# MainDAC.net
KiCad netlist of a schematic drawn in Altium Designer
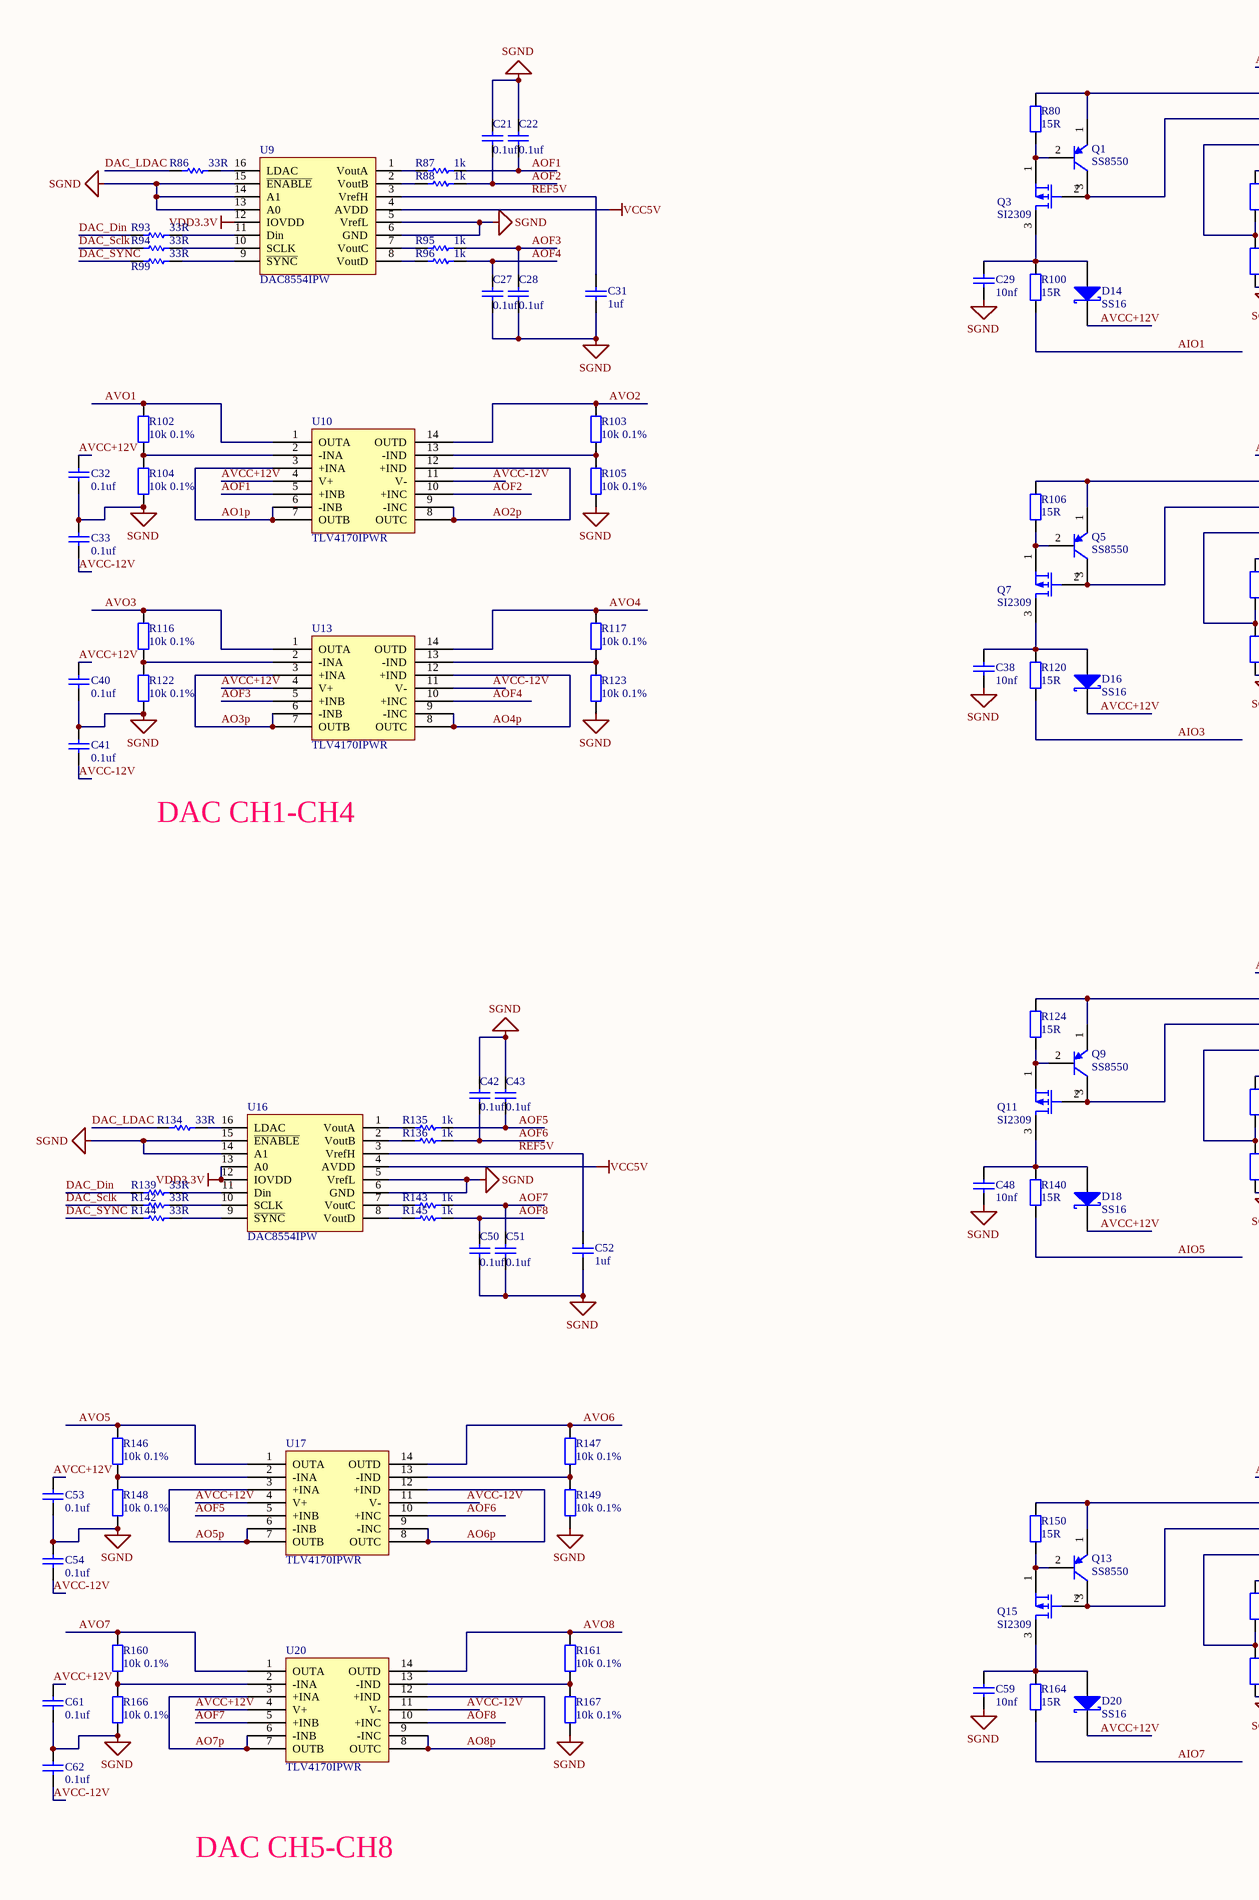
[diagram p0: MainDAC.SchDoc, left]
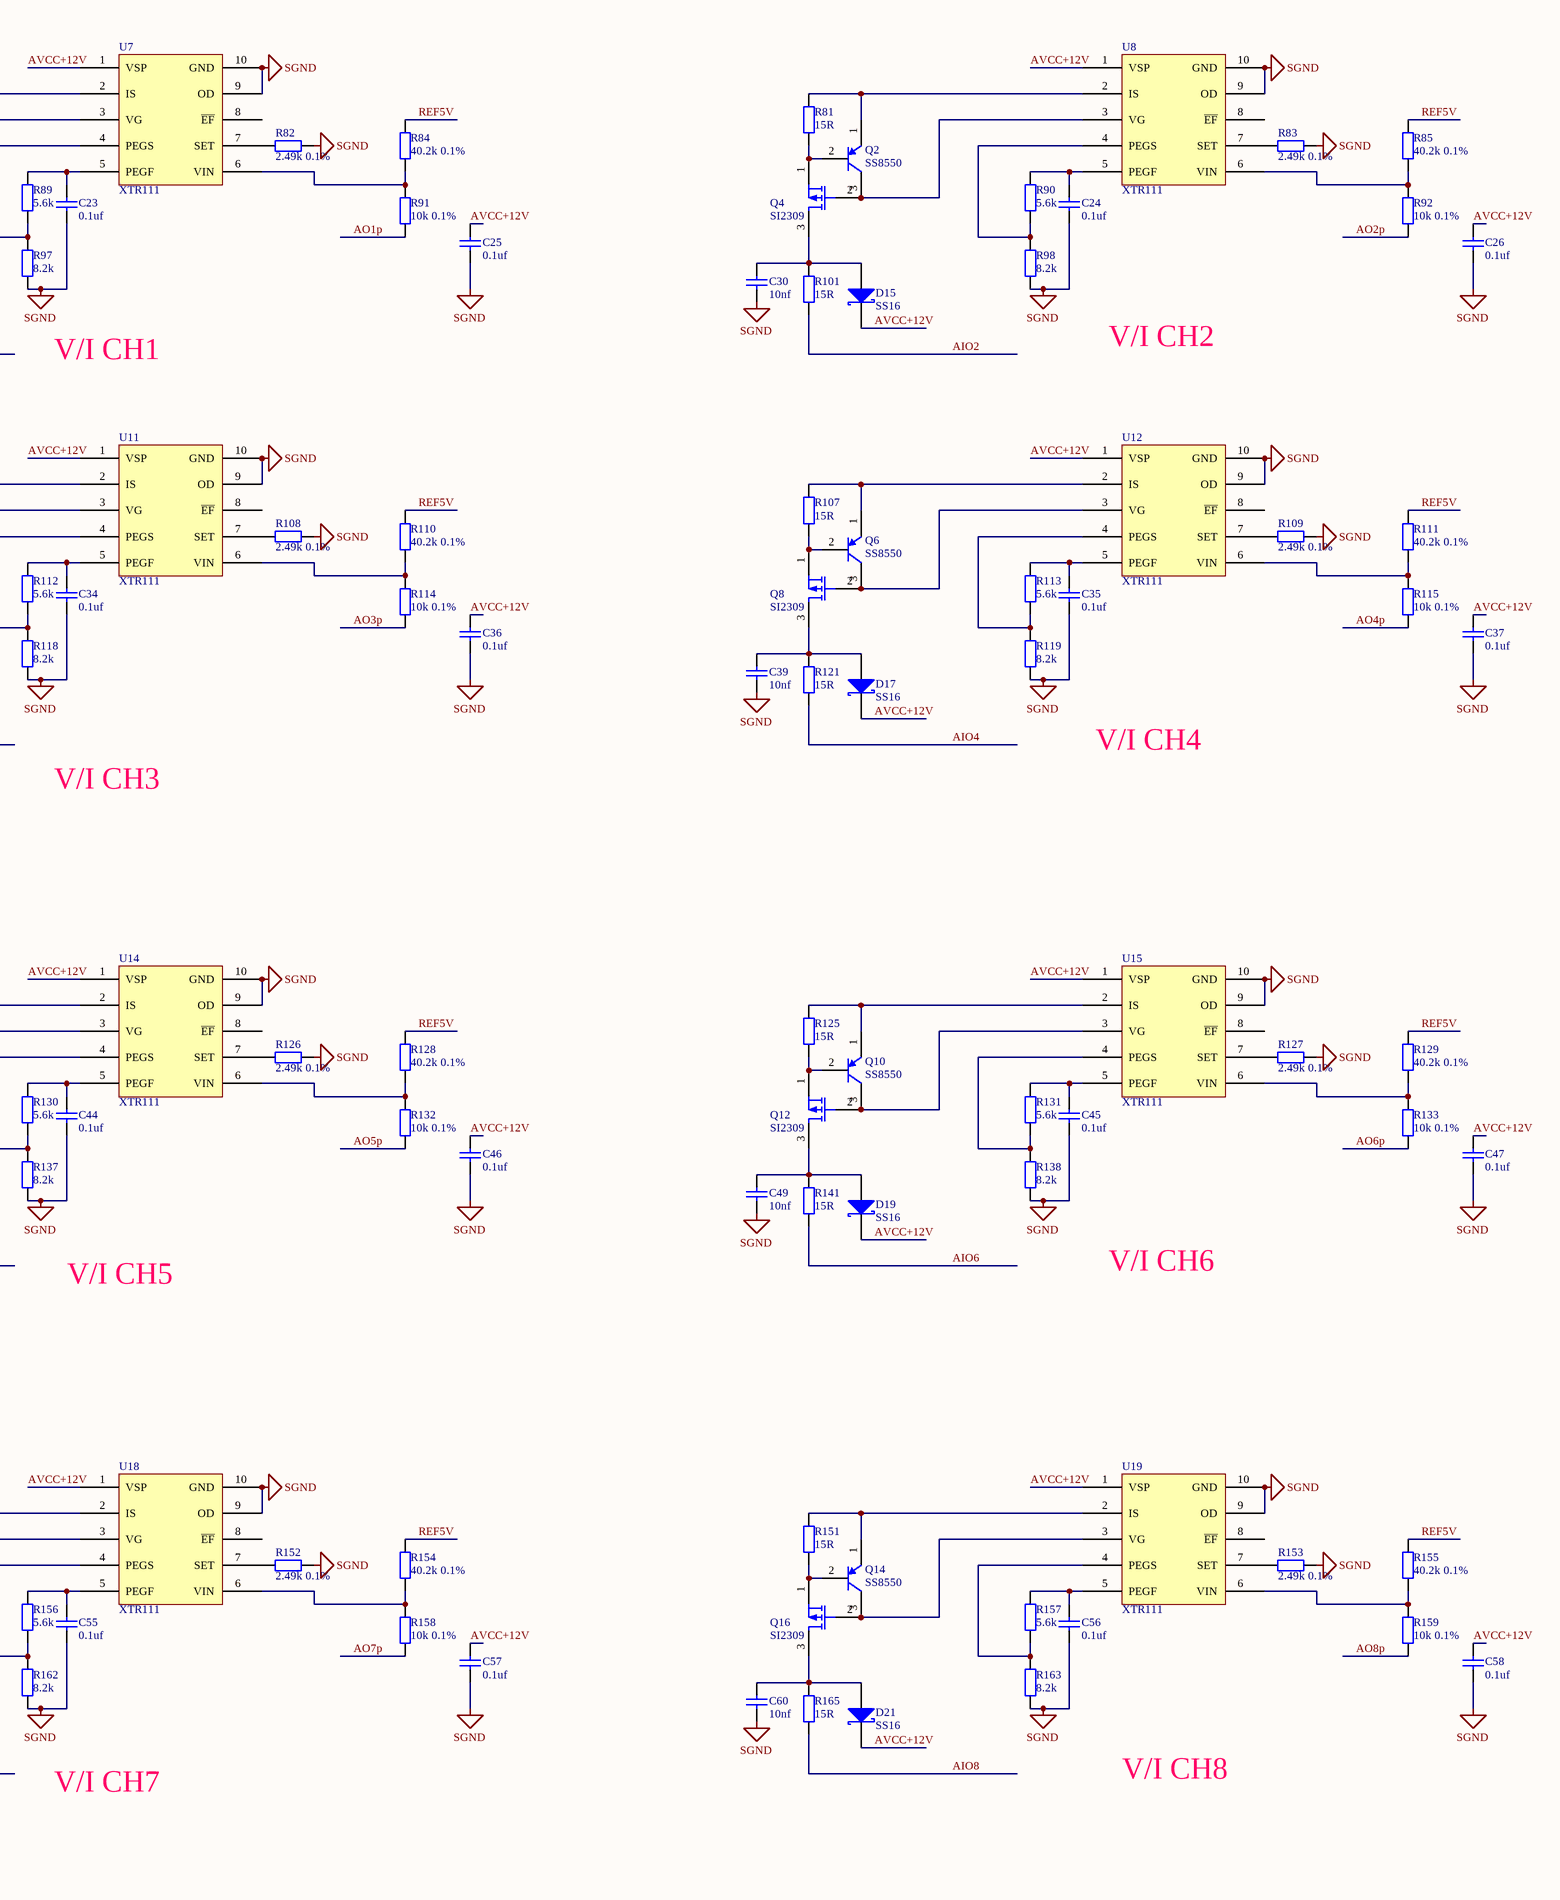
[diagram p1: MainDAC.SchDoc, right]

(export (version "E")
  (design (tool "Eeschema 10.0.6"))
  (components
    (comp (ref "C21")
      (value "0.1uf")
      (footprint "C0805")
      (description "Capacitor")
      (fields
        (field (name "MANUFACTURER") "Generic Components")
        (field (name "Comment") "Cap")
        (field (name "PUBLISHER") "Altium Hobart Technology Centre")
      )
      (libsource (lib "Miscellaneous Devices") (part "Cap"))
    )
    (comp (ref "C22")
      (value "0.1uf")
      (footprint "C0805")
      (description "Capacitor")
      (fields
        (field (name "MANUFACTURER") "Generic Components")
        (field (name "Comment") "Cap")
        (field (name "PUBLISHER") "Altium Hobart Technology Centre")
      )
      (libsource (lib "Miscellaneous Devices") (part "Cap"))
    )
    (comp (ref "C23")
      (value "0.1uf")
      (footprint "C0805")
      (description "Capacitor")
      (fields
        (field (name "MANUFACTURER") "Generic Components")
        (field (name "Comment") "Cap")
        (field (name "PUBLISHER") "Altium Hobart Technology Centre")
      )
      (libsource (lib "Miscellaneous Devices") (part "Cap"))
    )
    (comp (ref "C24")
      (value "0.1uf")
      (footprint "C0805")
      (description "Capacitor")
      (fields
        (field (name "MANUFACTURER") "Generic Components")
        (field (name "Comment") "Cap")
        (field (name "PUBLISHER") "Altium Hobart Technology Centre")
      )
      (libsource (lib "Miscellaneous Devices") (part "Cap"))
    )
    (comp (ref "C25")
      (value "0.1uf")
      (footprint "C0805")
      (description "Capacitor")
      (fields
        (field (name "MANUFACTURER") "Generic Components")
        (field (name "Comment") "Cap")
        (field (name "PUBLISHER") "Altium Hobart Technology Centre")
      )
      (libsource (lib "Miscellaneous Devices") (part "Cap"))
    )
    (comp (ref "C26")
      (value "0.1uf")
      (footprint "C0805")
      (description "Capacitor")
      (fields
        (field (name "MANUFACTURER") "Generic Components")
        (field (name "Comment") "Cap")
        (field (name "PUBLISHER") "Altium Hobart Technology Centre")
      )
      (libsource (lib "Miscellaneous Devices") (part "Cap"))
    )
    (comp (ref "C27")
      (value "0.1uf")
      (footprint "C0805")
      (description "Capacitor")
      (fields
        (field (name "MANUFACTURER") "Generic Components")
        (field (name "Comment") "Cap")
        (field (name "PUBLISHER") "Altium Hobart Technology Centre")
      )
      (libsource (lib "Miscellaneous Devices") (part "Cap"))
    )
    (comp (ref "C28")
      (value "0.1uf")
      (footprint "C0805")
      (description "Capacitor")
      (fields
        (field (name "MANUFACTURER") "Generic Components")
        (field (name "Comment") "Cap")
        (field (name "PUBLISHER") "Altium Hobart Technology Centre")
      )
      (libsource (lib "Miscellaneous Devices") (part "Cap"))
    )
    (comp (ref "C29")
      (value "10nf")
      (footprint "C0805")
      (description "Capacitor")
      (fields
        (field (name "MANUFACTURER") "Generic Components")
        (field (name "Comment") "Cap")
        (field (name "PUBLISHER") "Altium Hobart Technology Centre")
      )
      (libsource (lib "Miscellaneous Devices") (part "Cap"))
    )
    (comp (ref "C30")
      (value "10nf")
      (footprint "C0805")
      (description "Capacitor")
      (fields
        (field (name "MANUFACTURER") "Generic Components")
        (field (name "Comment") "Cap")
        (field (name "PUBLISHER") "Altium Hobart Technology Centre")
      )
      (libsource (lib "Miscellaneous Devices") (part "Cap"))
    )
    (comp (ref "C31")
      (value "1uf")
      (footprint "C0805")
      (description "Capacitor")
      (fields
        (field (name "MANUFACTURER") "Generic Components")
        (field (name "Comment") "Cap")
        (field (name "PUBLISHER") "Altium Hobart Technology Centre")
      )
      (libsource (lib "Miscellaneous Devices") (part "Cap"))
    )
    (comp (ref "C32")
      (value "0.1uf")
      (footprint "C0805")
      (description "Capacitor")
      (fields
        (field (name "MANUFACTURER") "Generic Components")
        (field (name "Comment") "Cap")
        (field (name "PUBLISHER") "Altium Hobart Technology Centre")
      )
      (libsource (lib "Miscellaneous Devices") (part "Cap"))
    )
    (comp (ref "C33")
      (value "0.1uf")
      (footprint "C0805")
      (description "Capacitor")
      (fields
        (field (name "MANUFACTURER") "Generic Components")
        (field (name "Comment") "Cap")
        (field (name "PUBLISHER") "Altium Hobart Technology Centre")
      )
      (libsource (lib "Miscellaneous Devices") (part "Cap"))
    )
    (comp (ref "C34")
      (value "0.1uf")
      (footprint "C0805")
      (description "Capacitor")
      (fields
        (field (name "MANUFACTURER") "Generic Components")
        (field (name "Comment") "Cap")
        (field (name "PUBLISHER") "Altium Hobart Technology Centre")
      )
      (libsource (lib "Miscellaneous Devices") (part "Cap"))
    )
    (comp (ref "C35")
      (value "0.1uf")
      (footprint "C0805")
      (description "Capacitor")
      (fields
        (field (name "MANUFACTURER") "Generic Components")
        (field (name "Comment") "Cap")
        (field (name "PUBLISHER") "Altium Hobart Technology Centre")
      )
      (libsource (lib "Miscellaneous Devices") (part "Cap"))
    )
    (comp (ref "C36")
      (value "0.1uf")
      (footprint "C0805")
      (description "Capacitor")
      (fields
        (field (name "MANUFACTURER") "Generic Components")
        (field (name "Comment") "Cap")
        (field (name "PUBLISHER") "Altium Hobart Technology Centre")
      )
      (libsource (lib "Miscellaneous Devices") (part "Cap"))
    )
    (comp (ref "C37")
      (value "0.1uf")
      (footprint "C0805")
      (description "Capacitor")
      (fields
        (field (name "MANUFACTURER") "Generic Components")
        (field (name "Comment") "Cap")
        (field (name "PUBLISHER") "Altium Hobart Technology Centre")
      )
      (libsource (lib "Miscellaneous Devices") (part "Cap"))
    )
    (comp (ref "C38")
      (value "10nf")
      (footprint "C0805")
      (description "Capacitor")
      (fields
        (field (name "MANUFACTURER") "Generic Components")
        (field (name "Comment") "Cap")
        (field (name "PUBLISHER") "Altium Hobart Technology Centre")
      )
      (libsource (lib "Miscellaneous Devices") (part "Cap"))
    )
    (comp (ref "C39")
      (value "10nf")
      (footprint "C0805")
      (description "Capacitor")
      (fields
        (field (name "MANUFACTURER") "Generic Components")
        (field (name "Comment") "Cap")
        (field (name "PUBLISHER") "Altium Hobart Technology Centre")
      )
      (libsource (lib "Miscellaneous Devices") (part "Cap"))
    )
    (comp (ref "C40")
      (value "0.1uf")
      (footprint "C0805")
      (description "Capacitor")
      (fields
        (field (name "MANUFACTURER") "Generic Components")
        (field (name "Comment") "Cap")
        (field (name "PUBLISHER") "Altium Hobart Technology Centre")
      )
      (libsource (lib "Miscellaneous Devices") (part "Cap"))
    )
    (comp (ref "C41")
      (value "0.1uf")
      (footprint "C0805")
      (description "Capacitor")
      (fields
        (field (name "MANUFACTURER") "Generic Components")
        (field (name "Comment") "Cap")
        (field (name "PUBLISHER") "Altium Hobart Technology Centre")
      )
      (libsource (lib "Miscellaneous Devices") (part "Cap"))
    )
    (comp (ref "C42")
      (value "0.1uf")
      (footprint "C0805")
      (description "Capacitor")
      (fields
        (field (name "MANUFACTURER") "Generic Components")
        (field (name "Comment") "Cap")
        (field (name "PUBLISHER") "Altium Hobart Technology Centre")
      )
      (libsource (lib "Miscellaneous Devices") (part "Cap"))
    )
    (comp (ref "C43")
      (value "0.1uf")
      (footprint "C0805")
      (description "Capacitor")
      (fields
        (field (name "MANUFACTURER") "Generic Components")
        (field (name "Comment") "Cap")
        (field (name "PUBLISHER") "Altium Hobart Technology Centre")
      )
      (libsource (lib "Miscellaneous Devices") (part "Cap"))
    )
    (comp (ref "C44")
      (value "0.1uf")
      (footprint "C0805")
      (description "Capacitor")
      (fields
        (field (name "MANUFACTURER") "Generic Components")
        (field (name "Comment") "Cap")
        (field (name "PUBLISHER") "Altium Hobart Technology Centre")
      )
      (libsource (lib "Miscellaneous Devices") (part "Cap"))
    )
    (comp (ref "C45")
      (value "0.1uf")
      (footprint "C0805")
      (description "Capacitor")
      (fields
        (field (name "MANUFACTURER") "Generic Components")
        (field (name "Comment") "Cap")
        (field (name "PUBLISHER") "Altium Hobart Technology Centre")
      )
      (libsource (lib "Miscellaneous Devices") (part "Cap"))
    )
    (comp (ref "C46")
      (value "0.1uf")
      (footprint "C0805")
      (description "Capacitor")
      (fields
        (field (name "MANUFACTURER") "Generic Components")
        (field (name "Comment") "Cap")
        (field (name "PUBLISHER") "Altium Hobart Technology Centre")
      )
      (libsource (lib "Miscellaneous Devices") (part "Cap"))
    )
    (comp (ref "C47")
      (value "0.1uf")
      (footprint "C0805")
      (description "Capacitor")
      (fields
        (field (name "MANUFACTURER") "Generic Components")
        (field (name "Comment") "Cap")
        (field (name "PUBLISHER") "Altium Hobart Technology Centre")
      )
      (libsource (lib "Miscellaneous Devices") (part "Cap"))
    )
    (comp (ref "C48")
      (value "10nf")
      (footprint "C0805")
      (description "Capacitor")
      (fields
        (field (name "MANUFACTURER") "Generic Components")
        (field (name "Comment") "Cap")
        (field (name "PUBLISHER") "Altium Hobart Technology Centre")
      )
      (libsource (lib "Miscellaneous Devices") (part "Cap"))
    )
    (comp (ref "C49")
      (value "10nf")
      (footprint "C0805")
      (description "Capacitor")
      (fields
        (field (name "MANUFACTURER") "Generic Components")
        (field (name "Comment") "Cap")
        (field (name "PUBLISHER") "Altium Hobart Technology Centre")
      )
      (libsource (lib "Miscellaneous Devices") (part "Cap"))
    )
    (comp (ref "C50")
      (value "0.1uf")
      (footprint "C0805")
      (description "Capacitor")
      (fields
        (field (name "MANUFACTURER") "Generic Components")
        (field (name "Comment") "Cap")
        (field (name "PUBLISHER") "Altium Hobart Technology Centre")
      )
      (libsource (lib "Miscellaneous Devices") (part "Cap"))
    )
    (comp (ref "C51")
      (value "0.1uf")
      (footprint "C0805")
      (description "Capacitor")
      (fields
        (field (name "MANUFACTURER") "Generic Components")
        (field (name "Comment") "Cap")
        (field (name "PUBLISHER") "Altium Hobart Technology Centre")
      )
      (libsource (lib "Miscellaneous Devices") (part "Cap"))
    )
    (comp (ref "C52")
      (value "1uf")
      (footprint "C0805")
      (description "Capacitor")
      (fields
        (field (name "MANUFACTURER") "Generic Components")
        (field (name "Comment") "Cap")
        (field (name "PUBLISHER") "Altium Hobart Technology Centre")
      )
      (libsource (lib "Miscellaneous Devices") (part "Cap"))
    )
    (comp (ref "C53")
      (value "0.1uf")
      (footprint "C0805")
      (description "Capacitor")
      (fields
        (field (name "MANUFACTURER") "Generic Components")
        (field (name "Comment") "Cap")
        (field (name "PUBLISHER") "Altium Hobart Technology Centre")
      )
      (libsource (lib "Miscellaneous Devices") (part "Cap"))
    )
    (comp (ref "C54")
      (value "0.1uf")
      (footprint "C0805")
      (description "Capacitor")
      (fields
        (field (name "MANUFACTURER") "Generic Components")
        (field (name "Comment") "Cap")
        (field (name "PUBLISHER") "Altium Hobart Technology Centre")
      )
      (libsource (lib "Miscellaneous Devices") (part "Cap"))
    )
    (comp (ref "C55")
      (value "0.1uf")
      (footprint "C0805")
      (description "Capacitor")
      (fields
        (field (name "MANUFACTURER") "Generic Components")
        (field (name "Comment") "Cap")
        (field (name "PUBLISHER") "Altium Hobart Technology Centre")
      )
      (libsource (lib "Miscellaneous Devices") (part "Cap"))
    )
    (comp (ref "C56")
      (value "0.1uf")
      (footprint "C0805")
      (description "Capacitor")
      (fields
        (field (name "MANUFACTURER") "Generic Components")
        (field (name "Comment") "Cap")
        (field (name "PUBLISHER") "Altium Hobart Technology Centre")
      )
      (libsource (lib "Miscellaneous Devices") (part "Cap"))
    )
    (comp (ref "C57")
      (value "0.1uf")
      (footprint "C0805")
      (description "Capacitor")
      (fields
        (field (name "MANUFACTURER") "Generic Components")
        (field (name "Comment") "Cap")
        (field (name "PUBLISHER") "Altium Hobart Technology Centre")
      )
      (libsource (lib "Miscellaneous Devices") (part "Cap"))
    )
    (comp (ref "C58")
      (value "0.1uf")
      (footprint "C0805")
      (description "Capacitor")
      (fields
        (field (name "MANUFACTURER") "Generic Components")
        (field (name "Comment") "Cap")
        (field (name "PUBLISHER") "Altium Hobart Technology Centre")
      )
      (libsource (lib "Miscellaneous Devices") (part "Cap"))
    )
    (comp (ref "C59")
      (value "10nf")
      (footprint "C0805")
      (description "Capacitor")
      (fields
        (field (name "MANUFACTURER") "Generic Components")
        (field (name "Comment") "Cap")
        (field (name "PUBLISHER") "Altium Hobart Technology Centre")
      )
      (libsource (lib "Miscellaneous Devices") (part "Cap"))
    )
    (comp (ref "C60")
      (value "10nf")
      (footprint "C0805")
      (description "Capacitor")
      (fields
        (field (name "MANUFACTURER") "Generic Components")
        (field (name "Comment") "Cap")
        (field (name "PUBLISHER") "Altium Hobart Technology Centre")
      )
      (libsource (lib "Miscellaneous Devices") (part "Cap"))
    )
    (comp (ref "C61")
      (value "0.1uf")
      (footprint "C0805")
      (description "Capacitor")
      (fields
        (field (name "MANUFACTURER") "Generic Components")
        (field (name "Comment") "Cap")
        (field (name "PUBLISHER") "Altium Hobart Technology Centre")
      )
      (libsource (lib "Miscellaneous Devices") (part "Cap"))
    )
    (comp (ref "C62")
      (value "0.1uf")
      (footprint "C0805")
      (description "Capacitor")
      (fields
        (field (name "MANUFACTURER") "Generic Components")
        (field (name "Comment") "Cap")
        (field (name "PUBLISHER") "Altium Hobart Technology Centre")
      )
      (libsource (lib "Miscellaneous Devices") (part "Cap"))
    )
    (comp (ref "D14")
      (value "SS16")
      (footprint "SMB")
      (description "Schottky Diode")
      (fields (field (name "PUBLISHER") "Altium Limited"))
      (libsource (lib "Miscellaneous Devices") (part "D Schottky"))
    )
    (comp (ref "D15")
      (value "SS16")
      (footprint "SMB")
      (description "Schottky Diode")
      (fields (field (name "PUBLISHER") "Altium Limited"))
      (libsource (lib "Miscellaneous Devices") (part "D Schottky"))
    )
    (comp (ref "D16")
      (value "SS16")
      (footprint "SMB")
      (description "Schottky Diode")
      (fields (field (name "PUBLISHER") "Altium Limited"))
      (libsource (lib "Miscellaneous Devices") (part "D Schottky"))
    )
    (comp (ref "D17")
      (value "SS16")
      (footprint "SMB")
      (description "Schottky Diode")
      (fields (field (name "PUBLISHER") "Altium Limited"))
      (libsource (lib "Miscellaneous Devices") (part "D Schottky"))
    )
    (comp (ref "D18")
      (value "SS16")
      (footprint "SMB")
      (description "Schottky Diode")
      (fields (field (name "PUBLISHER") "Altium Limited"))
      (libsource (lib "Miscellaneous Devices") (part "D Schottky"))
    )
    (comp (ref "D19")
      (value "SS16")
      (footprint "SMB")
      (description "Schottky Diode")
      (fields (field (name "PUBLISHER") "Altium Limited"))
      (libsource (lib "Miscellaneous Devices") (part "D Schottky"))
    )
    (comp (ref "D20")
      (value "SS16")
      (footprint "SMB")
      (description "Schottky Diode")
      (fields (field (name "PUBLISHER") "Altium Limited"))
      (libsource (lib "Miscellaneous Devices") (part "D Schottky"))
    )
    (comp (ref "D21")
      (value "SS16")
      (footprint "SMB")
      (description "Schottky Diode")
      (fields (field (name "PUBLISHER") "Altium Limited"))
      (libsource (lib "Miscellaneous Devices") (part "D Schottky"))
    )
    (comp (ref "Q1")
      (value "SS8550")
      (footprint "sot-23")
      (description "PNP General Purpose Amplifier")
      (fields (field (name "PUBLISHER") "Altium Limited"))
      (libsource (lib "Miscellaneous Devices") (part "2N3906"))
    )
    (comp (ref "Q2")
      (value "SS8550")
      (footprint "sot-23")
      (description "PNP General Purpose Amplifier")
      (fields (field (name "PUBLISHER") "Altium Limited"))
      (libsource (lib "Miscellaneous Devices") (part "2N3906"))
    )
    (comp (ref "Q3")
      (value "SI2309")
      (footprint "sot-23")
      (description "P-Channel MOSFET")
      (fields (field (name "PUBLISHER") "Altium Limited"))
      (libsource (lib "Miscellaneous Devices") (part "MOSFET-P"))
    )
    (comp (ref "Q4")
      (value "SI2309")
      (footprint "sot-23")
      (description "P-Channel MOSFET")
      (fields (field (name "PUBLISHER") "Altium Limited"))
      (libsource (lib "Miscellaneous Devices") (part "MOSFET-P"))
    )
    (comp (ref "Q5")
      (value "SS8550")
      (footprint "sot-23")
      (description "PNP General Purpose Amplifier")
      (fields (field (name "PUBLISHER") "Altium Limited"))
      (libsource (lib "Miscellaneous Devices") (part "2N3906"))
    )
    (comp (ref "Q6")
      (value "SS8550")
      (footprint "sot-23")
      (description "PNP General Purpose Amplifier")
      (fields (field (name "PUBLISHER") "Altium Limited"))
      (libsource (lib "Miscellaneous Devices") (part "2N3906"))
    )
    (comp (ref "Q7")
      (value "SI2309")
      (footprint "sot-23")
      (description "P-Channel MOSFET")
      (fields (field (name "PUBLISHER") "Altium Limited"))
      (libsource (lib "Miscellaneous Devices") (part "MOSFET-P"))
    )
    (comp (ref "Q8")
      (value "SI2309")
      (footprint "sot-23")
      (description "P-Channel MOSFET")
      (fields (field (name "PUBLISHER") "Altium Limited"))
      (libsource (lib "Miscellaneous Devices") (part "MOSFET-P"))
    )
    (comp (ref "Q9")
      (value "SS8550")
      (footprint "sot-23")
      (description "PNP General Purpose Amplifier")
      (fields (field (name "PUBLISHER") "Altium Limited"))
      (libsource (lib "Miscellaneous Devices") (part "2N3906"))
    )
    (comp (ref "Q10")
      (value "SS8550")
      (footprint "sot-23")
      (description "PNP General Purpose Amplifier")
      (fields (field (name "PUBLISHER") "Altium Limited"))
      (libsource (lib "Miscellaneous Devices") (part "2N3906"))
    )
    (comp (ref "Q11")
      (value "SI2309")
      (footprint "sot-23")
      (description "P-Channel MOSFET")
      (fields (field (name "PUBLISHER") "Altium Limited"))
      (libsource (lib "Miscellaneous Devices") (part "MOSFET-P"))
    )
    (comp (ref "Q12")
      (value "SI2309")
      (footprint "sot-23")
      (description "P-Channel MOSFET")
      (fields (field (name "PUBLISHER") "Altium Limited"))
      (libsource (lib "Miscellaneous Devices") (part "MOSFET-P"))
    )
    (comp (ref "Q13")
      (value "SS8550")
      (footprint "sot-23")
      (description "PNP General Purpose Amplifier")
      (fields (field (name "PUBLISHER") "Altium Limited"))
      (libsource (lib "Miscellaneous Devices") (part "2N3906"))
    )
    (comp (ref "Q14")
      (value "SS8550")
      (footprint "sot-23")
      (description "PNP General Purpose Amplifier")
      (fields (field (name "PUBLISHER") "Altium Limited"))
      (libsource (lib "Miscellaneous Devices") (part "2N3906"))
    )
    (comp (ref "Q15")
      (value "SI2309")
      (footprint "sot-23")
      (description "P-Channel MOSFET")
      (fields (field (name "PUBLISHER") "Altium Limited"))
      (libsource (lib "Miscellaneous Devices") (part "MOSFET-P"))
    )
    (comp (ref "Q16")
      (value "SI2309")
      (footprint "sot-23")
      (description "P-Channel MOSFET")
      (fields (field (name "PUBLISHER") "Altium Limited"))
      (libsource (lib "Miscellaneous Devices") (part "MOSFET-P"))
    )
    (comp (ref "R80")
      (value "15R")
      (footprint "0805")
      (fields (field (name "Comment") "Res2"))
      (libsource (lib "S1") (part "RES"))
    )
    (comp (ref "R81")
      (value "15R")
      (footprint "0805")
      (fields (field (name "Comment") "Res2"))
      (libsource (lib "S1") (part "RES"))
    )
    (comp (ref "R82")
      (value "2.49k 0.1%")
      (footprint "0805")
      (fields (field (name "Comment") "Res2"))
      (libsource (lib "") (part "RES_2"))
    )
    (comp (ref "R83")
      (value "2.49k 0.1%")
      (footprint "0805")
      (fields (field (name "Comment") "Res2"))
      (libsource (lib "") (part "RES_2"))
    )
    (comp (ref "R84")
      (value "40.2k 0.1%")
      (footprint "0805")
      (fields (field (name "Comment") "Res2"))
      (libsource (lib "S1") (part "RES"))
    )
    (comp (ref "R85")
      (value "40.2k 0.1%")
      (footprint "0805")
      (fields (field (name "Comment") "Res2"))
      (libsource (lib "S1") (part "RES"))
    )
    (comp (ref "R86")
      (value "33R")
      (footprint "0805")
      (description "Semiconductor Resistor")
      (fields (field (name "Comment") "Res Semi") (field (name "PUBLISHER") "Altium Limited"))
      (libsource (lib "Miscellaneous Devices") (part "Res Semi"))
    )
    (comp (ref "R87")
      (value "1k")
      (footprint "0805")
      (description "Semiconductor Resistor")
      (fields (field (name "Comment") "Res Semi") (field (name "PUBLISHER") "Altium Limited"))
      (libsource (lib "Miscellaneous Devices") (part "Res Semi"))
    )
    (comp (ref "R88")
      (value "1k")
      (footprint "0805")
      (description "Semiconductor Resistor")
      (fields (field (name "Comment") "Res Semi") (field (name "PUBLISHER") "Altium Limited"))
      (libsource (lib "Miscellaneous Devices") (part "Res Semi"))
    )
    (comp (ref "R89")
      (value "5.6k")
      (footprint "0805")
      (fields (field (name "Comment") "Res2"))
      (libsource (lib "S1") (part "RES"))
    )
    (comp (ref "R90")
      (value "5.6k")
      (footprint "0805")
      (fields (field (name "Comment") "Res2"))
      (libsource (lib "S1") (part "RES"))
    )
    (comp (ref "R91")
      (value "10k 0.1%")
      (footprint "0805")
      (fields (field (name "Comment") "Res2"))
      (libsource (lib "S1") (part "RES"))
    )
    (comp (ref "R92")
      (value "10k 0.1%")
      (footprint "0805")
      (fields (field (name "Comment") "Res2"))
      (libsource (lib "S1") (part "RES"))
    )
    (comp (ref "R93")
      (value "33R")
      (footprint "0805")
      (description "Semiconductor Resistor")
      (fields (field (name "Comment") "Res Semi") (field (name "PUBLISHER") "Altium Limited"))
      (libsource (lib "Miscellaneous Devices") (part "Res Semi"))
    )
    (comp (ref "R94")
      (value "33R")
      (footprint "0805")
      (description "Semiconductor Resistor")
      (fields (field (name "Comment") "Res Semi") (field (name "PUBLISHER") "Altium Limited"))
      (libsource (lib "Miscellaneous Devices") (part "Res Semi"))
    )
    (comp (ref "R95")
      (value "1k")
      (footprint "0805")
      (description "Semiconductor Resistor")
      (fields (field (name "Comment") "Res Semi") (field (name "PUBLISHER") "Altium Limited"))
      (libsource (lib "Miscellaneous Devices") (part "Res Semi"))
    )
    (comp (ref "R96")
      (value "1k")
      (footprint "0805")
      (description "Semiconductor Resistor")
      (fields (field (name "Comment") "Res Semi") (field (name "PUBLISHER") "Altium Limited"))
      (libsource (lib "Miscellaneous Devices") (part "Res Semi"))
    )
    (comp (ref "R97")
      (value "8.2k")
      (footprint "0805")
      (fields (field (name "Comment") "Res2"))
      (libsource (lib "S1") (part "RES"))
    )
    (comp (ref "R98")
      (value "8.2k")
      (footprint "0805")
      (fields (field (name "Comment") "Res2"))
      (libsource (lib "S1") (part "RES"))
    )
    (comp (ref "R99")
      (value "33R")
      (footprint "0805")
      (description "Semiconductor Resistor")
      (fields (field (name "Comment") "Res Semi") (field (name "PUBLISHER") "Altium Limited"))
      (libsource (lib "Miscellaneous Devices") (part "Res Semi"))
    )
    (comp (ref "R100")
      (value "15R")
      (footprint "0805")
      (fields (field (name "Comment") "Res2"))
      (libsource (lib "S1") (part "RES"))
    )
    (comp (ref "R101")
      (value "15R")
      (footprint "0805")
      (fields (field (name "Comment") "Res2"))
      (libsource (lib "S1") (part "RES"))
    )
    (comp (ref "R102")
      (value "10k 0.1%")
      (footprint "0805")
      (fields (field (name "Comment") "Res2"))
      (libsource (lib "") (part "RES_1"))
    )
    (comp (ref "R103")
      (value "10k 0.1%")
      (footprint "0805")
      (fields (field (name "Comment") "Res2"))
      (libsource (lib "S1") (part "RES"))
    )
    (comp (ref "R104")
      (value "10k 0.1%")
      (footprint "0805")
      (fields (field (name "Comment") "Res2"))
      (libsource (lib "") (part "RES_1"))
    )
    (comp (ref "R105")
      (value "10k 0.1%")
      (footprint "0805")
      (fields (field (name "Comment") "Res2"))
      (libsource (lib "S1") (part "RES"))
    )
    (comp (ref "R106")
      (value "15R")
      (footprint "0805")
      (fields (field (name "Comment") "Res2"))
      (libsource (lib "S1") (part "RES"))
    )
    (comp (ref "R107")
      (value "15R")
      (footprint "0805")
      (fields (field (name "Comment") "Res2"))
      (libsource (lib "S1") (part "RES"))
    )
    (comp (ref "R108")
      (value "2.49k 0.1%")
      (footprint "0805")
      (fields (field (name "Comment") "Res2"))
      (libsource (lib "") (part "RES_2"))
    )
    (comp (ref "R109")
      (value "2.49k 0.1%")
      (footprint "0805")
      (fields (field (name "Comment") "Res2"))
      (libsource (lib "") (part "RES_2"))
    )
    (comp (ref "R110")
      (value "40.2k 0.1%")
      (footprint "0805")
      (fields (field (name "Comment") "Res2"))
      (libsource (lib "S1") (part "RES"))
    )
    (comp (ref "R111")
      (value "40.2k 0.1%")
      (footprint "0805")
      (fields (field (name "Comment") "Res2"))
      (libsource (lib "S1") (part "RES"))
    )
    (comp (ref "R112")
      (value "5.6k")
      (footprint "0805")
      (fields (field (name "Comment") "Res2"))
      (libsource (lib "S1") (part "RES"))
    )
    (comp (ref "R113")
      (value "5.6k")
      (footprint "0805")
      (fields (field (name "Comment") "Res2"))
      (libsource (lib "S1") (part "RES"))
    )
    (comp (ref "R114")
      (value "10k 0.1%")
      (footprint "0805")
      (fields (field (name "Comment") "Res2"))
      (libsource (lib "S1") (part "RES"))
    )
    (comp (ref "R115")
      (value "10k 0.1%")
      (footprint "0805")
      (fields (field (name "Comment") "Res2"))
      (libsource (lib "S1") (part "RES"))
    )
    (comp (ref "R116")
      (value "10k 0.1%")
      (footprint "0805")
      (fields (field (name "Comment") "Res2"))
      (libsource (lib "") (part "RES_1"))
    )
    (comp (ref "R117")
      (value "10k 0.1%")
      (footprint "0805")
      (fields (field (name "Comment") "Res2"))
      (libsource (lib "S1") (part "RES"))
    )
    (comp (ref "R118")
      (value "8.2k")
      (footprint "0805")
      (fields (field (name "Comment") "Res2"))
      (libsource (lib "S1") (part "RES"))
    )
    (comp (ref "R119")
      (value "8.2k")
      (footprint "0805")
      (fields (field (name "Comment") "Res2"))
      (libsource (lib "S1") (part "RES"))
    )
    (comp (ref "R120")
      (value "15R")
      (footprint "0805")
      (fields (field (name "Comment") "Res2"))
      (libsource (lib "S1") (part "RES"))
    )
    (comp (ref "R121")
      (value "15R")
      (footprint "0805")
      (fields (field (name "Comment") "Res2"))
      (libsource (lib "S1") (part "RES"))
    )
    (comp (ref "R122")
      (value "10k 0.1%")
      (footprint "0805")
      (fields (field (name "Comment") "Res2"))
      (libsource (lib "") (part "RES_1"))
    )
    (comp (ref "R123")
      (value "10k 0.1%")
      (footprint "0805")
      (fields (field (name "Comment") "Res2"))
      (libsource (lib "S1") (part "RES"))
    )
    (comp (ref "R124")
      (value "15R")
      (footprint "0805")
      (fields (field (name "Comment") "Res2"))
      (libsource (lib "S1") (part "RES"))
    )
    (comp (ref "R125")
      (value "15R")
      (footprint "0805")
      (fields (field (name "Comment") "Res2"))
      (libsource (lib "S1") (part "RES"))
    )
    (comp (ref "R126")
      (value "2.49k 0.1%")
      (footprint "0805")
      (fields (field (name "Comment") "Res2"))
      (libsource (lib "") (part "RES_2"))
    )
    (comp (ref "R127")
      (value "2.49k 0.1%")
      (footprint "0805")
      (fields (field (name "Comment") "Res2"))
      (libsource (lib "") (part "RES_2"))
    )
    (comp (ref "R128")
      (value "40.2k 0.1%")
      (footprint "0805")
      (fields (field (name "Comment") "Res2"))
      (libsource (lib "S1") (part "RES"))
    )
    (comp (ref "R129")
      (value "40.2k 0.1%")
      (footprint "0805")
      (fields (field (name "Comment") "Res2"))
      (libsource (lib "S1") (part "RES"))
    )
    (comp (ref "R130")
      (value "5.6k")
      (footprint "0805")
      (fields (field (name "Comment") "Res2"))
      (libsource (lib "S1") (part "RES"))
    )
    (comp (ref "R131")
      (value "5.6k")
      (footprint "0805")
      (fields (field (name "Comment") "Res2"))
      (libsource (lib "S1") (part "RES"))
    )
    (comp (ref "R132")
      (value "10k 0.1%")
      (footprint "0805")
      (fields (field (name "Comment") "Res2"))
      (libsource (lib "S1") (part "RES"))
    )
    (comp (ref "R133")
      (value "10k 0.1%")
      (footprint "0805")
      (fields (field (name "Comment") "Res2"))
      (libsource (lib "S1") (part "RES"))
    )
    (comp (ref "R134")
      (value "33R")
      (footprint "0805")
      (description "Semiconductor Resistor")
      (fields (field (name "Comment") "Res Semi") (field (name "PUBLISHER") "Altium Limited"))
      (libsource (lib "Miscellaneous Devices") (part "Res Semi"))
    )
    (comp (ref "R135")
      (value "1k")
      (footprint "0805")
      (description "Semiconductor Resistor")
      (fields (field (name "Comment") "Res Semi") (field (name "PUBLISHER") "Altium Limited"))
      (libsource (lib "Miscellaneous Devices") (part "Res Semi"))
    )
    (comp (ref "R136")
      (value "1k")
      (footprint "0805")
      (description "Semiconductor Resistor")
      (fields (field (name "Comment") "Res Semi") (field (name "PUBLISHER") "Altium Limited"))
      (libsource (lib "Miscellaneous Devices") (part "Res Semi"))
    )
    (comp (ref "R137")
      (value "8.2k")
      (footprint "0805")
      (fields (field (name "Comment") "Res2"))
      (libsource (lib "S1") (part "RES"))
    )
    (comp (ref "R138")
      (value "8.2k")
      (footprint "0805")
      (fields (field (name "Comment") "Res2"))
      (libsource (lib "S1") (part "RES"))
    )
    (comp (ref "R139")
      (value "33R")
      (footprint "0805")
      (description "Semiconductor Resistor")
      (fields (field (name "Comment") "Res Semi") (field (name "PUBLISHER") "Altium Limited"))
      (libsource (lib "Miscellaneous Devices") (part "Res Semi"))
    )
    (comp (ref "R140")
      (value "15R")
      (footprint "0805")
      (fields (field (name "Comment") "Res2"))
      (libsource (lib "S1") (part "RES"))
    )
    (comp (ref "R141")
      (value "15R")
      (footprint "0805")
      (fields (field (name "Comment") "Res2"))
      (libsource (lib "S1") (part "RES"))
    )
    (comp (ref "R142")
      (value "33R")
      (footprint "0805")
      (description "Semiconductor Resistor")
      (fields (field (name "Comment") "Res Semi") (field (name "PUBLISHER") "Altium Limited"))
      (libsource (lib "Miscellaneous Devices") (part "Res Semi"))
    )
    (comp (ref "R143")
      (value "1k")
      (footprint "0805")
      (description "Semiconductor Resistor")
      (fields (field (name "Comment") "Res Semi") (field (name "PUBLISHER") "Altium Limited"))
      (libsource (lib "Miscellaneous Devices") (part "Res Semi"))
    )
    (comp (ref "R144")
      (value "33R")
      (footprint "0805")
      (description "Semiconductor Resistor")
      (fields (field (name "Comment") "Res Semi") (field (name "PUBLISHER") "Altium Limited"))
      (libsource (lib "Miscellaneous Devices") (part "Res Semi"))
    )
    (comp (ref "R145")
      (value "1k")
      (footprint "0805")
      (description "Semiconductor Resistor")
      (fields (field (name "Comment") "Res Semi") (field (name "PUBLISHER") "Altium Limited"))
      (libsource (lib "Miscellaneous Devices") (part "Res Semi"))
    )
    (comp (ref "R146")
      (value "10k 0.1%")
      (footprint "0805")
      (fields (field (name "Comment") "Res2"))
      (libsource (lib "") (part "RES_1"))
    )
    (comp (ref "R147")
      (value "10k 0.1%")
      (footprint "0805")
      (fields (field (name "Comment") "Res2"))
      (libsource (lib "S1") (part "RES"))
    )
    (comp (ref "R148")
      (value "10k 0.1%")
      (footprint "0805")
      (fields (field (name "Comment") "Res2"))
      (libsource (lib "") (part "RES_1"))
    )
    (comp (ref "R149")
      (value "10k 0.1%")
      (footprint "0805")
      (fields (field (name "Comment") "Res2"))
      (libsource (lib "S1") (part "RES"))
    )
    (comp (ref "R150")
      (value "15R")
      (footprint "0805")
      (fields (field (name "Comment") "Res2"))
      (libsource (lib "S1") (part "RES"))
    )
    (comp (ref "R151")
      (value "15R")
      (footprint "0805")
      (fields (field (name "Comment") "Res2"))
      (libsource (lib "S1") (part "RES"))
    )
    (comp (ref "R152")
      (value "2.49k 0.1%")
      (footprint "0805")
      (fields (field (name "Comment") "Res2"))
      (libsource (lib "") (part "RES_2"))
    )
    (comp (ref "R153")
      (value "2.49k 0.1%")
      (footprint "0805")
      (fields (field (name "Comment") "Res2"))
      (libsource (lib "") (part "RES_2"))
    )
    (comp (ref "R154")
      (value "40.2k 0.1%")
      (footprint "0805")
      (fields (field (name "Comment") "Res2"))
      (libsource (lib "S1") (part "RES"))
    )
    (comp (ref "R155")
      (value "40.2k 0.1%")
      (footprint "0805")
      (fields (field (name "Comment") "Res2"))
      (libsource (lib "S1") (part "RES"))
    )
    (comp (ref "R156")
      (value "5.6k")
      (footprint "0805")
      (fields (field (name "Comment") "Res2"))
      (libsource (lib "S1") (part "RES"))
    )
    (comp (ref "R157")
      (value "5.6k")
      (footprint "0805")
      (fields (field (name "Comment") "Res2"))
      (libsource (lib "S1") (part "RES"))
    )
    (comp (ref "R158")
      (value "10k 0.1%")
      (footprint "0805")
      (fields (field (name "Comment") "Res2"))
      (libsource (lib "S1") (part "RES"))
    )
    (comp (ref "R159")
      (value "10k 0.1%")
      (footprint "0805")
      (fields (field (name "Comment") "Res2"))
      (libsource (lib "S1") (part "RES"))
    )
    (comp (ref "R160")
      (value "10k 0.1%")
      (footprint "0805")
      (fields (field (name "Comment") "Res2"))
      (libsource (lib "") (part "RES_1"))
    )
    (comp (ref "R161")
      (value "10k 0.1%")
      (footprint "0805")
      (fields (field (name "Comment") "Res2"))
      (libsource (lib "S1") (part "RES"))
    )
    (comp (ref "R162")
      (value "8.2k")
      (footprint "0805")
      (fields (field (name "Comment") "Res2"))
      (libsource (lib "S1") (part "RES"))
    )
    (comp (ref "R163")
      (value "8.2k")
      (footprint "0805")
      (fields (field (name "Comment") "Res2"))
      (libsource (lib "S1") (part "RES"))
    )
    (comp (ref "R164")
      (value "15R")
      (footprint "0805")
      (fields (field (name "Comment") "Res2"))
      (libsource (lib "S1") (part "RES"))
    )
    (comp (ref "R165")
      (value "15R")
      (footprint "0805")
      (fields (field (name "Comment") "Res2"))
      (libsource (lib "S1") (part "RES"))
    )
    (comp (ref "R166")
      (value "10k 0.1%")
      (footprint "0805")
      (fields (field (name "Comment") "Res2"))
      (libsource (lib "") (part "RES_1"))
    )
    (comp (ref "R167")
      (value "10k 0.1%")
      (footprint "0805")
      (fields (field (name "Comment") "Res2"))
      (libsource (lib "S1") (part "RES"))
    )
    (comp (ref "U7") (value "XTR111") (footprint "TSSOP-10_P") (libsource (lib "斜测仪") (part "XTR111")))
    (comp (ref "U8") (value "XTR111") (footprint "TSSOP-10_P") (libsource (lib "斜测仪") (part "XTR111")))
    (comp (ref "U9")
      (value "DAC8554IPW")
      (footprint "TSSOP16")
      (libsource (lib "常用器件库_SCH") (part "DAC8554"))
    )
    (comp (ref "U10")
      (value "TLV4170IPWR")
      (footprint "WSOP14*0.65")
      (libsource (lib "斜测仪") (part "TLV4170"))
    )
    (comp (ref "U11") (value "XTR111") (footprint "TSSOP-10_P") (libsource (lib "斜测仪") (part "XTR111")))
    (comp (ref "U12") (value "XTR111") (footprint "TSSOP-10_P") (libsource (lib "斜测仪") (part "XTR111")))
    (comp (ref "U13")
      (value "TLV4170IPWR")
      (footprint "WSOP14*0.65")
      (libsource (lib "斜测仪") (part "TLV4170"))
    )
    (comp (ref "U14") (value "XTR111") (footprint "TSSOP-10_P") (libsource (lib "斜测仪") (part "XTR111")))
    (comp (ref "U15") (value "XTR111") (footprint "TSSOP-10_P") (libsource (lib "斜测仪") (part "XTR111")))
    (comp (ref "U16")
      (value "DAC8554IPW")
      (footprint "TSSOP16")
      (libsource (lib "常用器件库_SCH") (part "DAC8554"))
    )
    (comp (ref "U17")
      (value "TLV4170IPWR")
      (footprint "WSOP14*0.65")
      (libsource (lib "斜测仪") (part "TLV4170"))
    )
    (comp (ref "U18") (value "XTR111") (footprint "TSSOP-10_P") (libsource (lib "斜测仪") (part "XTR111")))
    (comp (ref "U19") (value "XTR111") (footprint "TSSOP-10_P") (libsource (lib "斜测仪") (part "XTR111")))
    (comp (ref "U20")
      (value "TLV4170IPWR")
      (footprint "WSOP14*0.65")
      (libsource (lib "斜测仪") (part "TLV4170"))
    )
  )
  (nets
    (net (code "1") (name "/AIO1") (class "Default")
      (node (ref "R100") (pin "2") (pinfunction "2_2") (pintype "passive"))
    )
    (net (code "2") (name "/AIO2") (class "Default")
      (node (ref "R101") (pin "2") (pinfunction "2_2") (pintype "passive"))
    )
    (net (code "3") (name "/AIO3") (class "Default")
      (node (ref "R120") (pin "2") (pinfunction "2_2") (pintype "passive"))
    )
    (net (code "4") (name "/AIO4") (class "Default")
      (node (ref "R121") (pin "2") (pinfunction "2_2") (pintype "passive"))
    )
    (net (code "5") (name "/AIO5") (class "Default")
      (node (ref "R140") (pin "2") (pinfunction "2_2") (pintype "passive"))
    )
    (net (code "6") (name "/AIO6") (class "Default")
      (node (ref "R141") (pin "2") (pinfunction "2_2") (pintype "passive"))
    )
    (net (code "7") (name "/AIO7") (class "Default")
      (node (ref "R164") (pin "2") (pinfunction "2_2") (pintype "passive"))
    )
    (net (code "8") (name "/AIO8") (class "Default")
      (node (ref "R165") (pin "2") (pinfunction "2_2") (pintype "passive"))
    )
    (net (code "9") (name "/AO1p") (class "Default")
      (node (ref "R91") (pin "2") (pinfunction "2_2") (pintype "passive"))
      (node (ref "U10") (pin "3") (pinfunction "+INA_3") (pintype "passive"))
      (node (ref "U10") (pin "6") (pinfunction "-INB_6") (pintype "passive"))
      (node (ref "U10") (pin "7") (pinfunction "OUTB_7") (pintype "passive"))
    )
    (net (code "10") (name "/AO2p") (class "Default")
      (node (ref "R92") (pin "2") (pinfunction "2_2") (pintype "passive"))
      (node (ref "U10") (pin "12") (pinfunction "+IND_12") (pintype "passive"))
      (node (ref "U10") (pin "8") (pinfunction "OUTC_8") (pintype "passive"))
      (node (ref "U10") (pin "9") (pinfunction "-INC_9") (pintype "passive"))
    )
    (net (code "11") (name "/AO3p") (class "Default")
      (node (ref "R114") (pin "2") (pinfunction "2_2") (pintype "passive"))
      (node (ref "U13") (pin "3") (pinfunction "+INA_3") (pintype "passive"))
      (node (ref "U13") (pin "6") (pinfunction "-INB_6") (pintype "passive"))
      (node (ref "U13") (pin "7") (pinfunction "OUTB_7") (pintype "passive"))
    )
    (net (code "12") (name "/AO4p") (class "Default")
      (node (ref "R115") (pin "2") (pinfunction "2_2") (pintype "passive"))
      (node (ref "U13") (pin "12") (pinfunction "+IND_12") (pintype "passive"))
      (node (ref "U13") (pin "8") (pinfunction "OUTC_8") (pintype "passive"))
      (node (ref "U13") (pin "9") (pinfunction "-INC_9") (pintype "passive"))
    )
    (net (code "13") (name "/AO5p") (class "Default")
      (node (ref "R132") (pin "2") (pinfunction "2_2") (pintype "passive"))
      (node (ref "U17") (pin "3") (pinfunction "+INA_3") (pintype "passive"))
      (node (ref "U17") (pin "6") (pinfunction "-INB_6") (pintype "passive"))
      (node (ref "U17") (pin "7") (pinfunction "OUTB_7") (pintype "passive"))
    )
    (net (code "14") (name "/AO6p") (class "Default")
      (node (ref "R133") (pin "2") (pinfunction "2_2") (pintype "passive"))
      (node (ref "U17") (pin "12") (pinfunction "+IND_12") (pintype "passive"))
      (node (ref "U17") (pin "8") (pinfunction "OUTC_8") (pintype "passive"))
      (node (ref "U17") (pin "9") (pinfunction "-INC_9") (pintype "passive"))
    )
    (net (code "15") (name "/AO7p") (class "Default")
      (node (ref "R158") (pin "2") (pinfunction "2_2") (pintype "passive"))
      (node (ref "U20") (pin "3") (pinfunction "+INA_3") (pintype "passive"))
      (node (ref "U20") (pin "6") (pinfunction "-INB_6") (pintype "passive"))
      (node (ref "U20") (pin "7") (pinfunction "OUTB_7") (pintype "passive"))
    )
    (net (code "16") (name "/AO8p") (class "Default")
      (node (ref "R159") (pin "2") (pinfunction "2_2") (pintype "passive"))
      (node (ref "U20") (pin "12") (pinfunction "+IND_12") (pintype "passive"))
      (node (ref "U20") (pin "8") (pinfunction "OUTC_8") (pintype "passive"))
      (node (ref "U20") (pin "9") (pinfunction "-INC_9") (pintype "passive"))
    )
    (net (code "17") (name "/AOF1") (class "Default")
      (node (ref "C22") (pin "2") (pinfunction "2_2") (pintype "passive"))
      (node (ref "R87") (pin "1") (pinfunction "1_1") (pintype "passive"))
      (node (ref "U10") (pin "5") (pinfunction "+INB_5") (pintype "passive"))
    )
    (net (code "18") (name "/AOF2") (class "Default")
      (node (ref "C21") (pin "2") (pinfunction "2_2") (pintype "passive"))
      (node (ref "R88") (pin "1") (pinfunction "1_1") (pintype "passive"))
      (node (ref "U10") (pin "10") (pinfunction "+INC_10") (pintype "passive"))
    )
    (net (code "19") (name "/AOF3") (class "Default")
      (node (ref "C28") (pin "1") (pinfunction "1_1") (pintype "passive"))
      (node (ref "R95") (pin "1") (pinfunction "1_1") (pintype "passive"))
      (node (ref "U13") (pin "5") (pinfunction "+INB_5") (pintype "passive"))
    )
    (net (code "20") (name "/AOF4") (class "Default")
      (node (ref "C27") (pin "1") (pinfunction "1_1") (pintype "passive"))
      (node (ref "R96") (pin "1") (pinfunction "1_1") (pintype "passive"))
      (node (ref "U13") (pin "10") (pinfunction "+INC_10") (pintype "passive"))
    )
    (net (code "21") (name "/AOF5") (class "Default")
      (node (ref "C43") (pin "2") (pinfunction "2_2") (pintype "passive"))
      (node (ref "R135") (pin "1") (pinfunction "1_1") (pintype "passive"))
      (node (ref "U17") (pin "5") (pinfunction "+INB_5") (pintype "passive"))
    )
    (net (code "22") (name "/AOF6") (class "Default")
      (node (ref "C42") (pin "2") (pinfunction "2_2") (pintype "passive"))
      (node (ref "R136") (pin "1") (pinfunction "1_1") (pintype "passive"))
      (node (ref "U17") (pin "10") (pinfunction "+INC_10") (pintype "passive"))
    )
    (net (code "23") (name "/AOF7") (class "Default")
      (node (ref "C51") (pin "1") (pinfunction "1_1") (pintype "passive"))
      (node (ref "R143") (pin "1") (pinfunction "1_1") (pintype "passive"))
      (node (ref "U20") (pin "5") (pinfunction "+INB_5") (pintype "passive"))
    )
    (net (code "24") (name "/AOF8") (class "Default")
      (node (ref "C50") (pin "1") (pinfunction "1_1") (pintype "passive"))
      (node (ref "R145") (pin "1") (pinfunction "1_1") (pintype "passive"))
      (node (ref "U20") (pin "10") (pinfunction "+INC_10") (pintype "passive"))
    )
    (net (code "25") (name "/AVCC+12V") (class "Default")
      (node (ref "C25") (pin "1") (pinfunction "1_1") (pintype "passive"))
      (node (ref "C26") (pin "1") (pinfunction "1_1") (pintype "passive"))
      (node (ref "C32") (pin "1") (pinfunction "1_1") (pintype "passive"))
      (node (ref "C36") (pin "1") (pinfunction "1_1") (pintype "passive"))
      (node (ref "C37") (pin "1") (pinfunction "1_1") (pintype "passive"))
      (node (ref "C40") (pin "1") (pinfunction "1_1") (pintype "passive"))
      (node (ref "C46") (pin "1") (pinfunction "1_1") (pintype "passive"))
      (node (ref "C47") (pin "1") (pinfunction "1_1") (pintype "passive"))
      (node (ref "C53") (pin "1") (pinfunction "1_1") (pintype "passive"))
      (node (ref "C57") (pin "1") (pinfunction "1_1") (pintype "passive"))
      (node (ref "C58") (pin "1") (pinfunction "1_1") (pintype "passive"))
      (node (ref "C61") (pin "1") (pinfunction "1_1") (pintype "passive"))
      (node (ref "D14") (pin "2") (pinfunction "K_2") (pintype "passive"))
      (node (ref "D15") (pin "2") (pinfunction "K_2") (pintype "passive"))
      (node (ref "D16") (pin "2") (pinfunction "K_2") (pintype "passive"))
      (node (ref "D17") (pin "2") (pinfunction "K_2") (pintype "passive"))
      (node (ref "D18") (pin "2") (pinfunction "K_2") (pintype "passive"))
      (node (ref "D19") (pin "2") (pinfunction "K_2") (pintype "passive"))
      (node (ref "D20") (pin "2") (pinfunction "K_2") (pintype "passive"))
      (node (ref "D21") (pin "2") (pinfunction "K_2") (pintype "passive"))
      (node (ref "U10") (pin "4") (pinfunction "V+_4") (pintype "passive"))
      (node (ref "U11") (pin "1") (pinfunction "VSP_1") (pintype "passive"))
      (node (ref "U12") (pin "1") (pinfunction "VSP_1") (pintype "passive"))
      (node (ref "U13") (pin "4") (pinfunction "V+_4") (pintype "passive"))
      (node (ref "U14") (pin "1") (pinfunction "VSP_1") (pintype "passive"))
      (node (ref "U15") (pin "1") (pinfunction "VSP_1") (pintype "passive"))
      (node (ref "U17") (pin "4") (pinfunction "V+_4") (pintype "passive"))
      (node (ref "U18") (pin "1") (pinfunction "VSP_1") (pintype "passive"))
      (node (ref "U19") (pin "1") (pinfunction "VSP_1") (pintype "passive"))
      (node (ref "U20") (pin "4") (pinfunction "V+_4") (pintype "passive"))
      (node (ref "U7") (pin "1") (pinfunction "VSP_1") (pintype "passive"))
      (node (ref "U8") (pin "1") (pinfunction "VSP_1") (pintype "passive"))
    )
    (net (code "26") (name "/AVCC-12V") (class "Default")
      (node (ref "C33") (pin "2") (pinfunction "2_2") (pintype "passive"))
      (node (ref "C41") (pin "2") (pinfunction "2_2") (pintype "passive"))
      (node (ref "C54") (pin "2") (pinfunction "2_2") (pintype "passive"))
      (node (ref "C62") (pin "2") (pinfunction "2_2") (pintype "passive"))
      (node (ref "U10") (pin "11") (pinfunction "V-_11") (pintype "passive"))
      (node (ref "U13") (pin "11") (pinfunction "V-_11") (pintype "passive"))
      (node (ref "U17") (pin "11") (pinfunction "V-_11") (pintype "passive"))
      (node (ref "U20") (pin "11") (pinfunction "V-_11") (pintype "passive"))
    )
    (net (code "27") (name "/AVO1") (class "Default")
      (node (ref "R102") (pin "1") (pinfunction "1_1") (pintype "passive"))
      (node (ref "U10") (pin "1") (pinfunction "OUTA_1") (pintype "passive"))
    )
    (net (code "28") (name "/AVO2") (class "Default")
      (node (ref "R103") (pin "1") (pinfunction "1_1") (pintype "passive"))
      (node (ref "U10") (pin "14") (pinfunction "OUTD_14") (pintype "passive"))
    )
    (net (code "29") (name "/AVO3") (class "Default")
      (node (ref "R116") (pin "1") (pinfunction "1_1") (pintype "passive"))
      (node (ref "U13") (pin "1") (pinfunction "OUTA_1") (pintype "passive"))
    )
    (net (code "30") (name "/AVO4") (class "Default")
      (node (ref "R117") (pin "1") (pinfunction "1_1") (pintype "passive"))
      (node (ref "U13") (pin "14") (pinfunction "OUTD_14") (pintype "passive"))
    )
    (net (code "31") (name "/AVO5") (class "Default")
      (node (ref "R146") (pin "1") (pinfunction "1_1") (pintype "passive"))
      (node (ref "U17") (pin "1") (pinfunction "OUTA_1") (pintype "passive"))
    )
    (net (code "32") (name "/AVO6") (class "Default")
      (node (ref "R147") (pin "1") (pinfunction "1_1") (pintype "passive"))
      (node (ref "U17") (pin "14") (pinfunction "OUTD_14") (pintype "passive"))
    )
    (net (code "33") (name "/AVO7") (class "Default")
      (node (ref "R160") (pin "1") (pinfunction "1_1") (pintype "passive"))
      (node (ref "U20") (pin "1") (pinfunction "OUTA_1") (pintype "passive"))
    )
    (net (code "34") (name "/AVO8") (class "Default")
      (node (ref "R161") (pin "1") (pinfunction "1_1") (pintype "passive"))
      (node (ref "U20") (pin "14") (pinfunction "OUTD_14") (pintype "passive"))
    )
    (net (code "35") (name "/DAC_Din") (class "Default")
      (node (ref "R139") (pin "2") (pinfunction "2_2") (pintype "passive"))
      (node (ref "R93") (pin "2") (pinfunction "2_2") (pintype "passive"))
    )
    (net (code "36") (name "/DAC_LDAC") (class "Default")
      (node (ref "R134") (pin "2") (pinfunction "2_2") (pintype "passive"))
      (node (ref "R86") (pin "2") (pinfunction "2_2") (pintype "passive"))
    )
    (net (code "37") (name "/DAC_SYNC") (class "Default")
      (node (ref "R144") (pin "2") (pinfunction "2_2") (pintype "passive"))
      (node (ref "R99") (pin "2") (pinfunction "2_2") (pintype "passive"))
    )
    (net (code "38") (name "/DAC_Sclk") (class "Default")
      (node (ref "R142") (pin "2") (pinfunction "2_2") (pintype "passive"))
      (node (ref "R94") (pin "2") (pinfunction "2_2") (pintype "passive"))
    )
    (net (code "39") (name "/REF5V") (class "Default")
      (node (ref "C31") (pin "2") (pinfunction "2_2") (pintype "passive"))
      (node (ref "C52") (pin "2") (pinfunction "2_2") (pintype "passive"))
      (node (ref "R110") (pin "1") (pinfunction "1_1") (pintype "passive"))
      (node (ref "R111") (pin "1") (pinfunction "1_1") (pintype "passive"))
      (node (ref "R128") (pin "1") (pinfunction "1_1") (pintype "passive"))
      (node (ref "R129") (pin "1") (pinfunction "1_1") (pintype "passive"))
      (node (ref "R154") (pin "1") (pinfunction "1_1") (pintype "passive"))
      (node (ref "R155") (pin "1") (pinfunction "1_1") (pintype "passive"))
      (node (ref "R84") (pin "1") (pinfunction "1_1") (pintype "passive"))
      (node (ref "R85") (pin "1") (pinfunction "1_1") (pintype "passive"))
      (node (ref "U16") (pin "3") (pinfunction "VrefH_3") (pintype "passive"))
      (node (ref "U9") (pin "3") (pinfunction "VrefH_3") (pintype "passive"))
    )
    (net (code "40") (name "Net-(D14-A)") (class "Default")
      (node (ref "C29") (pin "1") (pinfunction "1_1") (pintype "passive"))
      (node (ref "D14") (pin "1") (pinfunction "A_1") (pintype "passive"))
      (node (ref "Q3") (pin "3") (pinfunction "D_3") (pintype "passive"))
      (node (ref "R100") (pin "1") (pinfunction "1_1") (pintype "passive"))
    )
    (net (code "41") (name "Net-(D15-A)") (class "Default")
      (node (ref "C30") (pin "1") (pinfunction "1_1") (pintype "passive"))
      (node (ref "D15") (pin "1") (pinfunction "A_1") (pintype "passive"))
      (node (ref "Q4") (pin "3") (pinfunction "D_3") (pintype "passive"))
      (node (ref "R101") (pin "1") (pinfunction "1_1") (pintype "passive"))
    )
    (net (code "42") (name "Net-(D16-A)") (class "Default")
      (node (ref "C38") (pin "1") (pinfunction "1_1") (pintype "passive"))
      (node (ref "D16") (pin "1") (pinfunction "A_1") (pintype "passive"))
      (node (ref "Q7") (pin "3") (pinfunction "D_3") (pintype "passive"))
      (node (ref "R120") (pin "1") (pinfunction "1_1") (pintype "passive"))
    )
    (net (code "43") (name "Net-(D17-A)") (class "Default")
      (node (ref "C39") (pin "1") (pinfunction "1_1") (pintype "passive"))
      (node (ref "D17") (pin "1") (pinfunction "A_1") (pintype "passive"))
      (node (ref "Q8") (pin "3") (pinfunction "D_3") (pintype "passive"))
      (node (ref "R121") (pin "1") (pinfunction "1_1") (pintype "passive"))
    )
    (net (code "44") (name "Net-(D18-A)") (class "Default")
      (node (ref "C48") (pin "1") (pinfunction "1_1") (pintype "passive"))
      (node (ref "D18") (pin "1") (pinfunction "A_1") (pintype "passive"))
      (node (ref "Q11") (pin "3") (pinfunction "D_3") (pintype "passive"))
      (node (ref "R140") (pin "1") (pinfunction "1_1") (pintype "passive"))
    )
    (net (code "45") (name "Net-(D19-A)") (class "Default")
      (node (ref "C49") (pin "1") (pinfunction "1_1") (pintype "passive"))
      (node (ref "D19") (pin "1") (pinfunction "A_1") (pintype "passive"))
      (node (ref "Q12") (pin "3") (pinfunction "D_3") (pintype "passive"))
      (node (ref "R141") (pin "1") (pinfunction "1_1") (pintype "passive"))
    )
    (net (code "46") (name "Net-(D20-A)") (class "Default")
      (node (ref "C59") (pin "1") (pinfunction "1_1") (pintype "passive"))
      (node (ref "D20") (pin "1") (pinfunction "A_1") (pintype "passive"))
      (node (ref "Q15") (pin "3") (pinfunction "D_3") (pintype "passive"))
      (node (ref "R164") (pin "1") (pinfunction "1_1") (pintype "passive"))
    )
    (net (code "47") (name "Net-(D21-A)") (class "Default")
      (node (ref "C60") (pin "1") (pinfunction "1_1") (pintype "passive"))
      (node (ref "D21") (pin "1") (pinfunction "A_1") (pintype "passive"))
      (node (ref "Q16") (pin "3") (pinfunction "D_3") (pintype "passive"))
      (node (ref "R165") (pin "1") (pinfunction "1_1") (pintype "passive"))
    )
    (net (code "48") (name "Net-(Q1-B)") (class "Default")
      (node (ref "Q1") (pin "2") (pinfunction "B_2") (pintype "passive"))
      (node (ref "Q3") (pin "1") (pinfunction "S_1") (pintype "passive"))
      (node (ref "R80") (pin "2") (pinfunction "2_2") (pintype "passive"))
    )
    (net (code "49") (name "Net-(Q1-C)") (class "Default")
      (node (ref "Q1") (pin "3") (pinfunction "C_3") (pintype "passive"))
      (node (ref "Q3") (pin "2") (pinfunction "G_2") (pintype "passive"))
      (node (ref "U7") (pin "3") (pinfunction "VG_3") (pintype "passive"))
    )
    (net (code "50") (name "Net-(Q1-E)") (class "Default")
      (node (ref "Q1") (pin "1") (pinfunction "E_1") (pintype "passive"))
      (node (ref "R80") (pin "1") (pinfunction "1_1") (pintype "passive"))
      (node (ref "U7") (pin "2") (pinfunction "IS_2") (pintype "passive"))
    )
    (net (code "51") (name "Net-(Q2-B)") (class "Default")
      (node (ref "Q2") (pin "2") (pinfunction "B_2") (pintype "passive"))
      (node (ref "Q4") (pin "1") (pinfunction "S_1") (pintype "passive"))
      (node (ref "R81") (pin "2") (pinfunction "2_2") (pintype "passive"))
    )
    (net (code "52") (name "Net-(Q2-C)") (class "Default")
      (node (ref "Q2") (pin "3") (pinfunction "C_3") (pintype "passive"))
      (node (ref "Q4") (pin "2") (pinfunction "G_2") (pintype "passive"))
      (node (ref "U8") (pin "3") (pinfunction "VG_3") (pintype "passive"))
    )
    (net (code "53") (name "Net-(Q2-E)") (class "Default")
      (node (ref "Q2") (pin "1") (pinfunction "E_1") (pintype "passive"))
      (node (ref "R81") (pin "1") (pinfunction "1_1") (pintype "passive"))
      (node (ref "U8") (pin "2") (pinfunction "IS_2") (pintype "passive"))
    )
    (net (code "54") (name "Net-(Q5-B)") (class "Default")
      (node (ref "Q5") (pin "2") (pinfunction "B_2") (pintype "passive"))
      (node (ref "Q7") (pin "1") (pinfunction "S_1") (pintype "passive"))
      (node (ref "R106") (pin "2") (pinfunction "2_2") (pintype "passive"))
    )
    (net (code "55") (name "Net-(Q5-C)") (class "Default")
      (node (ref "Q5") (pin "3") (pinfunction "C_3") (pintype "passive"))
      (node (ref "Q7") (pin "2") (pinfunction "G_2") (pintype "passive"))
      (node (ref "U11") (pin "3") (pinfunction "VG_3") (pintype "passive"))
    )
    (net (code "56") (name "Net-(Q5-E)") (class "Default")
      (node (ref "Q5") (pin "1") (pinfunction "E_1") (pintype "passive"))
      (node (ref "R106") (pin "1") (pinfunction "1_1") (pintype "passive"))
      (node (ref "U11") (pin "2") (pinfunction "IS_2") (pintype "passive"))
    )
    (net (code "57") (name "Net-(Q6-B)") (class "Default")
      (node (ref "Q6") (pin "2") (pinfunction "B_2") (pintype "passive"))
      (node (ref "Q8") (pin "1") (pinfunction "S_1") (pintype "passive"))
      (node (ref "R107") (pin "2") (pinfunction "2_2") (pintype "passive"))
    )
    (net (code "58") (name "Net-(Q6-C)") (class "Default")
      (node (ref "Q6") (pin "3") (pinfunction "C_3") (pintype "passive"))
      (node (ref "Q8") (pin "2") (pinfunction "G_2") (pintype "passive"))
      (node (ref "U12") (pin "3") (pinfunction "VG_3") (pintype "passive"))
    )
    (net (code "59") (name "Net-(Q6-E)") (class "Default")
      (node (ref "Q6") (pin "1") (pinfunction "E_1") (pintype "passive"))
      (node (ref "R107") (pin "1") (pinfunction "1_1") (pintype "passive"))
      (node (ref "U12") (pin "2") (pinfunction "IS_2") (pintype "passive"))
    )
    (net (code "60") (name "Net-(Q9-E)") (class "Default")
      (node (ref "Q9") (pin "1") (pinfunction "E_1") (pintype "passive"))
      (node (ref "R124") (pin "1") (pinfunction "1_1") (pintype "passive"))
      (node (ref "U14") (pin "2") (pinfunction "IS_2") (pintype "passive"))
    )
    (net (code "61") (name "Net-(Q10-B)") (class "Default")
      (node (ref "Q10") (pin "2") (pinfunction "B_2") (pintype "passive"))
      (node (ref "Q12") (pin "1") (pinfunction "S_1") (pintype "passive"))
      (node (ref "R125") (pin "2") (pinfunction "2_2") (pintype "passive"))
    )
    (net (code "62") (name "Net-(Q10-C)") (class "Default")
      (node (ref "Q10") (pin "3") (pinfunction "C_3") (pintype "passive"))
      (node (ref "Q12") (pin "2") (pinfunction "G_2") (pintype "passive"))
      (node (ref "U15") (pin "3") (pinfunction "VG_3") (pintype "passive"))
    )
    (net (code "63") (name "Net-(Q10-E)") (class "Default")
      (node (ref "Q10") (pin "1") (pinfunction "E_1") (pintype "passive"))
      (node (ref "R125") (pin "1") (pinfunction "1_1") (pintype "passive"))
      (node (ref "U15") (pin "2") (pinfunction "IS_2") (pintype "passive"))
    )
    (net (code "64") (name "Net-(Q11-G)") (class "Default")
      (node (ref "Q11") (pin "2") (pinfunction "G_2") (pintype "passive"))
      (node (ref "Q9") (pin "3") (pinfunction "C_3") (pintype "passive"))
      (node (ref "U14") (pin "3") (pinfunction "VG_3") (pintype "passive"))
    )
    (net (code "65") (name "Net-(Q11-S)") (class "Default")
      (node (ref "Q11") (pin "1") (pinfunction "S_1") (pintype "passive"))
      (node (ref "Q9") (pin "2") (pinfunction "B_2") (pintype "passive"))
      (node (ref "R124") (pin "2") (pinfunction "2_2") (pintype "passive"))
    )
    (net (code "66") (name "Net-(Q13-B)") (class "Default")
      (node (ref "Q13") (pin "2") (pinfunction "B_2") (pintype "passive"))
      (node (ref "Q15") (pin "1") (pinfunction "S_1") (pintype "passive"))
      (node (ref "R150") (pin "2") (pinfunction "2_2") (pintype "passive"))
    )
    (net (code "67") (name "Net-(Q13-C)") (class "Default")
      (node (ref "Q13") (pin "3") (pinfunction "C_3") (pintype "passive"))
      (node (ref "Q15") (pin "2") (pinfunction "G_2") (pintype "passive"))
      (node (ref "U18") (pin "3") (pinfunction "VG_3") (pintype "passive"))
    )
    (net (code "68") (name "Net-(Q13-E)") (class "Default")
      (node (ref "Q13") (pin "1") (pinfunction "E_1") (pintype "passive"))
      (node (ref "R150") (pin "1") (pinfunction "1_1") (pintype "passive"))
      (node (ref "U18") (pin "2") (pinfunction "IS_2") (pintype "passive"))
    )
    (net (code "69") (name "Net-(Q14-B)") (class "Default")
      (node (ref "Q14") (pin "2") (pinfunction "B_2") (pintype "passive"))
      (node (ref "Q16") (pin "1") (pinfunction "S_1") (pintype "passive"))
      (node (ref "R151") (pin "2") (pinfunction "2_2") (pintype "passive"))
    )
    (net (code "70") (name "Net-(Q14-C)") (class "Default")
      (node (ref "Q14") (pin "3") (pinfunction "C_3") (pintype "passive"))
      (node (ref "Q16") (pin "2") (pinfunction "G_2") (pintype "passive"))
      (node (ref "U19") (pin "3") (pinfunction "VG_3") (pintype "passive"))
    )
    (net (code "71") (name "Net-(Q14-E)") (class "Default")
      (node (ref "Q14") (pin "1") (pinfunction "E_1") (pintype "passive"))
      (node (ref "R151") (pin "1") (pinfunction "1_1") (pintype "passive"))
      (node (ref "U19") (pin "2") (pinfunction "IS_2") (pintype "passive"))
    )
    (net (code "72") (name "Net-(U7-PEGF)") (class "Default")
      (node (ref "C23") (pin "1") (pinfunction "1_1") (pintype "passive"))
      (node (ref "R89") (pin "1") (pinfunction "1_1") (pintype "passive"))
      (node (ref "U7") (pin "5") (pinfunction "PEGF_5") (pintype "passive"))
    )
    (net (code "73") (name "Net-(U7-PEGS)") (class "Default")
      (node (ref "R89") (pin "2") (pinfunction "2_2") (pintype "passive"))
      (node (ref "R97") (pin "1") (pinfunction "1_1") (pintype "passive"))
      (node (ref "U7") (pin "4") (pinfunction "PEGS_4") (pintype "passive"))
    )
    (net (code "74") (name "Net-(U7-SET)") (class "Default")
      (node (ref "R82") (pin "1") (pinfunction "1_1") (pintype "passive"))
      (node (ref "U7") (pin "7") (pinfunction "SET_7") (pintype "passive"))
    )
    (net (code "75") (name "Net-(U7-VIN)") (class "Default")
      (node (ref "R84") (pin "2") (pinfunction "2_2") (pintype "passive"))
      (node (ref "R91") (pin "1") (pinfunction "1_1") (pintype "passive"))
      (node (ref "U7") (pin "6") (pinfunction "VIN_6") (pintype "passive"))
    )
    (net (code "76") (name "Net-(U8-PEGF)") (class "Default")
      (node (ref "C24") (pin "1") (pinfunction "1_1") (pintype "passive"))
      (node (ref "R90") (pin "1") (pinfunction "1_1") (pintype "passive"))
      (node (ref "U8") (pin "5") (pinfunction "PEGF_5") (pintype "passive"))
    )
    (net (code "77") (name "Net-(U8-PEGS)") (class "Default")
      (node (ref "R90") (pin "2") (pinfunction "2_2") (pintype "passive"))
      (node (ref "R98") (pin "1") (pinfunction "1_1") (pintype "passive"))
      (node (ref "U8") (pin "4") (pinfunction "PEGS_4") (pintype "passive"))
    )
    (net (code "78") (name "Net-(U8-SET)") (class "Default")
      (node (ref "R83") (pin "1") (pinfunction "1_1") (pintype "passive"))
      (node (ref "U8") (pin "7") (pinfunction "SET_7") (pintype "passive"))
    )
    (net (code "79") (name "Net-(U8-VIN)") (class "Default")
      (node (ref "R85") (pin "2") (pinfunction "2_2") (pintype "passive"))
      (node (ref "R92") (pin "1") (pinfunction "1_1") (pintype "passive"))
      (node (ref "U8") (pin "6") (pinfunction "VIN_6") (pintype "passive"))
    )
    (net (code "80") (name "Net-(U9-Din)") (class "Default")
      (node (ref "R93") (pin "1") (pinfunction "1_1") (pintype "passive"))
      (node (ref "U9") (pin "11") (pinfunction "Din_11") (pintype "passive"))
    )
    (net (code "81") (name "Net-(U9-LDAC)") (class "Default")
      (node (ref "R86") (pin "1") (pinfunction "1_1") (pintype "passive"))
      (node (ref "U9") (pin "16") (pinfunction "LDAC_16") (pintype "passive"))
    )
    (net (code "82") (name "Net-(U9-SCLK)") (class "Default")
      (node (ref "R94") (pin "1") (pinfunction "1_1") (pintype "passive"))
      (node (ref "U9") (pin "10") (pinfunction "SCLK_10") (pintype "passive"))
    )
    (net (code "83") (name "Net-(U9-VoutA)") (class "Default")
      (node (ref "R87") (pin "2") (pinfunction "2_2") (pintype "passive"))
      (node (ref "U9") (pin "1") (pinfunction "VoutA_1") (pintype "passive"))
    )
    (net (code "84") (name "Net-(U9-VoutB)") (class "Default")
      (node (ref "R88") (pin "2") (pinfunction "2_2") (pintype "passive"))
      (node (ref "U9") (pin "2") (pinfunction "VoutB_2") (pintype "passive"))
    )
    (net (code "85") (name "Net-(U9-VoutC)") (class "Default")
      (node (ref "R95") (pin "2") (pinfunction "2_2") (pintype "passive"))
      (node (ref "U9") (pin "7") (pinfunction "VoutC_7") (pintype "passive"))
    )
    (net (code "86") (name "Net-(U9-VoutD)") (class "Default")
      (node (ref "R96") (pin "2") (pinfunction "2_2") (pintype "passive"))
      (node (ref "U9") (pin "8") (pinfunction "VoutD_8") (pintype "passive"))
    )
    (net (code "87") (name "Net-(U9-~{SYNC})") (class "Default")
      (node (ref "R99") (pin "1") (pinfunction "1_1") (pintype "passive"))
      (node (ref "U9") (pin "9") (pinfunction "~{SYNC}_9") (pintype "passive"))
    )
    (net (code "88") (name "Net-(U10--INA)") (class "Default")
      (node (ref "R102") (pin "2") (pinfunction "2_2") (pintype "passive"))
      (node (ref "R104") (pin "1") (pinfunction "1_1") (pintype "passive"))
      (node (ref "U10") (pin "2") (pinfunction "-INA_2") (pintype "passive"))
    )
    (net (code "89") (name "Net-(U10--IND)") (class "Default")
      (node (ref "R103") (pin "2") (pinfunction "2_2") (pintype "passive"))
      (node (ref "R105") (pin "1") (pinfunction "1_1") (pintype "passive"))
      (node (ref "U10") (pin "13") (pinfunction "-IND_13") (pintype "passive"))
    )
    (net (code "90") (name "Net-(U11-PEGF)") (class "Default")
      (node (ref "C34") (pin "1") (pinfunction "1_1") (pintype "passive"))
      (node (ref "R112") (pin "1") (pinfunction "1_1") (pintype "passive"))
      (node (ref "U11") (pin "5") (pinfunction "PEGF_5") (pintype "passive"))
    )
    (net (code "91") (name "Net-(U11-PEGS)") (class "Default")
      (node (ref "R112") (pin "2") (pinfunction "2_2") (pintype "passive"))
      (node (ref "R118") (pin "1") (pinfunction "1_1") (pintype "passive"))
      (node (ref "U11") (pin "4") (pinfunction "PEGS_4") (pintype "passive"))
    )
    (net (code "92") (name "Net-(U11-SET)") (class "Default")
      (node (ref "R108") (pin "1") (pinfunction "1_1") (pintype "passive"))
      (node (ref "U11") (pin "7") (pinfunction "SET_7") (pintype "passive"))
    )
    (net (code "93") (name "Net-(U11-VIN)") (class "Default")
      (node (ref "R110") (pin "2") (pinfunction "2_2") (pintype "passive"))
      (node (ref "R114") (pin "1") (pinfunction "1_1") (pintype "passive"))
      (node (ref "U11") (pin "6") (pinfunction "VIN_6") (pintype "passive"))
    )
    (net (code "94") (name "Net-(U12-PEGF)") (class "Default")
      (node (ref "C35") (pin "1") (pinfunction "1_1") (pintype "passive"))
      (node (ref "R113") (pin "1") (pinfunction "1_1") (pintype "passive"))
      (node (ref "U12") (pin "5") (pinfunction "PEGF_5") (pintype "passive"))
    )
    (net (code "95") (name "Net-(U12-PEGS)") (class "Default")
      (node (ref "R113") (pin "2") (pinfunction "2_2") (pintype "passive"))
      (node (ref "R119") (pin "1") (pinfunction "1_1") (pintype "passive"))
      (node (ref "U12") (pin "4") (pinfunction "PEGS_4") (pintype "passive"))
    )
    (net (code "96") (name "Net-(U12-SET)") (class "Default")
      (node (ref "R109") (pin "1") (pinfunction "1_1") (pintype "passive"))
      (node (ref "U12") (pin "7") (pinfunction "SET_7") (pintype "passive"))
    )
    (net (code "97") (name "Net-(U12-VIN)") (class "Default")
      (node (ref "R111") (pin "2") (pinfunction "2_2") (pintype "passive"))
      (node (ref "R115") (pin "1") (pinfunction "1_1") (pintype "passive"))
      (node (ref "U12") (pin "6") (pinfunction "VIN_6") (pintype "passive"))
    )
    (net (code "98") (name "Net-(U13--INA)") (class "Default")
      (node (ref "R116") (pin "2") (pinfunction "2_2") (pintype "passive"))
      (node (ref "R122") (pin "1") (pinfunction "1_1") (pintype "passive"))
      (node (ref "U13") (pin "2") (pinfunction "-INA_2") (pintype "passive"))
    )
    (net (code "99") (name "Net-(U13--IND)") (class "Default")
      (node (ref "R117") (pin "2") (pinfunction "2_2") (pintype "passive"))
      (node (ref "R123") (pin "1") (pinfunction "1_1") (pintype "passive"))
      (node (ref "U13") (pin "13") (pinfunction "-IND_13") (pintype "passive"))
    )
    (net (code "100") (name "Net-(U14-PEGF)") (class "Default")
      (node (ref "C44") (pin "1") (pinfunction "1_1") (pintype "passive"))
      (node (ref "R130") (pin "1") (pinfunction "1_1") (pintype "passive"))
      (node (ref "U14") (pin "5") (pinfunction "PEGF_5") (pintype "passive"))
    )
    (net (code "101") (name "Net-(U14-PEGS)") (class "Default")
      (node (ref "R130") (pin "2") (pinfunction "2_2") (pintype "passive"))
      (node (ref "R137") (pin "1") (pinfunction "1_1") (pintype "passive"))
      (node (ref "U14") (pin "4") (pinfunction "PEGS_4") (pintype "passive"))
    )
    (net (code "102") (name "Net-(U14-SET)") (class "Default")
      (node (ref "R126") (pin "1") (pinfunction "1_1") (pintype "passive"))
      (node (ref "U14") (pin "7") (pinfunction "SET_7") (pintype "passive"))
    )
    (net (code "103") (name "Net-(U14-VIN)") (class "Default")
      (node (ref "R128") (pin "2") (pinfunction "2_2") (pintype "passive"))
      (node (ref "R132") (pin "1") (pinfunction "1_1") (pintype "passive"))
      (node (ref "U14") (pin "6") (pinfunction "VIN_6") (pintype "passive"))
    )
    (net (code "104") (name "Net-(U15-PEGF)") (class "Default")
      (node (ref "C45") (pin "1") (pinfunction "1_1") (pintype "passive"))
      (node (ref "R131") (pin "1") (pinfunction "1_1") (pintype "passive"))
      (node (ref "U15") (pin "5") (pinfunction "PEGF_5") (pintype "passive"))
    )
    (net (code "105") (name "Net-(U15-PEGS)") (class "Default")
      (node (ref "R131") (pin "2") (pinfunction "2_2") (pintype "passive"))
      (node (ref "R138") (pin "1") (pinfunction "1_1") (pintype "passive"))
      (node (ref "U15") (pin "4") (pinfunction "PEGS_4") (pintype "passive"))
    )
    (net (code "106") (name "Net-(U15-SET)") (class "Default")
      (node (ref "R127") (pin "1") (pinfunction "1_1") (pintype "passive"))
      (node (ref "U15") (pin "7") (pinfunction "SET_7") (pintype "passive"))
    )
    (net (code "107") (name "Net-(U15-VIN)") (class "Default")
      (node (ref "R129") (pin "2") (pinfunction "2_2") (pintype "passive"))
      (node (ref "R133") (pin "1") (pinfunction "1_1") (pintype "passive"))
      (node (ref "U15") (pin "6") (pinfunction "VIN_6") (pintype "passive"))
    )
    (net (code "108") (name "Net-(U16-Din)") (class "Default")
      (node (ref "R139") (pin "1") (pinfunction "1_1") (pintype "passive"))
      (node (ref "U16") (pin "11") (pinfunction "Din_11") (pintype "passive"))
    )
    (net (code "109") (name "Net-(U16-LDAC)") (class "Default")
      (node (ref "R134") (pin "1") (pinfunction "1_1") (pintype "passive"))
      (node (ref "U16") (pin "16") (pinfunction "LDAC_16") (pintype "passive"))
    )
    (net (code "110") (name "Net-(U16-SCLK)") (class "Default")
      (node (ref "R142") (pin "1") (pinfunction "1_1") (pintype "passive"))
      (node (ref "U16") (pin "10") (pinfunction "SCLK_10") (pintype "passive"))
    )
    (net (code "111") (name "Net-(U16-VoutA)") (class "Default")
      (node (ref "R135") (pin "2") (pinfunction "2_2") (pintype "passive"))
      (node (ref "U16") (pin "1") (pinfunction "VoutA_1") (pintype "passive"))
    )
    (net (code "112") (name "Net-(U16-VoutB)") (class "Default")
      (node (ref "R136") (pin "2") (pinfunction "2_2") (pintype "passive"))
      (node (ref "U16") (pin "2") (pinfunction "VoutB_2") (pintype "passive"))
    )
    (net (code "113") (name "Net-(U16-VoutC)") (class "Default")
      (node (ref "R143") (pin "2") (pinfunction "2_2") (pintype "passive"))
      (node (ref "U16") (pin "7") (pinfunction "VoutC_7") (pintype "passive"))
    )
    (net (code "114") (name "Net-(U16-VoutD)") (class "Default")
      (node (ref "R145") (pin "2") (pinfunction "2_2") (pintype "passive"))
      (node (ref "U16") (pin "8") (pinfunction "VoutD_8") (pintype "passive"))
    )
    (net (code "115") (name "Net-(U16-~{SYNC})") (class "Default")
      (node (ref "R144") (pin "1") (pinfunction "1_1") (pintype "passive"))
      (node (ref "U16") (pin "9") (pinfunction "~{SYNC}_9") (pintype "passive"))
    )
    (net (code "116") (name "Net-(U17--INA)") (class "Default")
      (node (ref "R146") (pin "2") (pinfunction "2_2") (pintype "passive"))
      (node (ref "R148") (pin "1") (pinfunction "1_1") (pintype "passive"))
      (node (ref "U17") (pin "2") (pinfunction "-INA_2") (pintype "passive"))
    )
    (net (code "117") (name "Net-(U17--IND)") (class "Default")
      (node (ref "R147") (pin "2") (pinfunction "2_2") (pintype "passive"))
      (node (ref "R149") (pin "1") (pinfunction "1_1") (pintype "passive"))
      (node (ref "U17") (pin "13") (pinfunction "-IND_13") (pintype "passive"))
    )
    (net (code "118") (name "Net-(U18-PEGF)") (class "Default")
      (node (ref "C55") (pin "1") (pinfunction "1_1") (pintype "passive"))
      (node (ref "R156") (pin "1") (pinfunction "1_1") (pintype "passive"))
      (node (ref "U18") (pin "5") (pinfunction "PEGF_5") (pintype "passive"))
    )
    (net (code "119") (name "Net-(U18-PEGS)") (class "Default")
      (node (ref "R156") (pin "2") (pinfunction "2_2") (pintype "passive"))
      (node (ref "R162") (pin "1") (pinfunction "1_1") (pintype "passive"))
      (node (ref "U18") (pin "4") (pinfunction "PEGS_4") (pintype "passive"))
    )
    (net (code "120") (name "Net-(U18-SET)") (class "Default")
      (node (ref "R152") (pin "1") (pinfunction "1_1") (pintype "passive"))
      (node (ref "U18") (pin "7") (pinfunction "SET_7") (pintype "passive"))
    )
    (net (code "121") (name "Net-(U18-VIN)") (class "Default")
      (node (ref "R154") (pin "2") (pinfunction "2_2") (pintype "passive"))
      (node (ref "R158") (pin "1") (pinfunction "1_1") (pintype "passive"))
      (node (ref "U18") (pin "6") (pinfunction "VIN_6") (pintype "passive"))
    )
    (net (code "122") (name "Net-(U19-PEGF)") (class "Default")
      (node (ref "C56") (pin "1") (pinfunction "1_1") (pintype "passive"))
      (node (ref "R157") (pin "1") (pinfunction "1_1") (pintype "passive"))
      (node (ref "U19") (pin "5") (pinfunction "PEGF_5") (pintype "passive"))
    )
    (net (code "123") (name "Net-(U19-PEGS)") (class "Default")
      (node (ref "R157") (pin "2") (pinfunction "2_2") (pintype "passive"))
      (node (ref "R163") (pin "1") (pinfunction "1_1") (pintype "passive"))
      (node (ref "U19") (pin "4") (pinfunction "PEGS_4") (pintype "passive"))
    )
    (net (code "124") (name "Net-(U19-SET)") (class "Default")
      (node (ref "R153") (pin "1") (pinfunction "1_1") (pintype "passive"))
      (node (ref "U19") (pin "7") (pinfunction "SET_7") (pintype "passive"))
    )
    (net (code "125") (name "Net-(U19-VIN)") (class "Default")
      (node (ref "R155") (pin "2") (pinfunction "2_2") (pintype "passive"))
      (node (ref "R159") (pin "1") (pinfunction "1_1") (pintype "passive"))
      (node (ref "U19") (pin "6") (pinfunction "VIN_6") (pintype "passive"))
    )
    (net (code "126") (name "Net-(U20--INA)") (class "Default")
      (node (ref "R160") (pin "2") (pinfunction "2_2") (pintype "passive"))
      (node (ref "R166") (pin "1") (pinfunction "1_1") (pintype "passive"))
      (node (ref "U20") (pin "2") (pinfunction "-INA_2") (pintype "passive"))
    )
    (net (code "127") (name "Net-(U20--IND)") (class "Default")
      (node (ref "R161") (pin "2") (pinfunction "2_2") (pintype "passive"))
      (node (ref "R167") (pin "1") (pinfunction "1_1") (pintype "passive"))
      (node (ref "U20") (pin "13") (pinfunction "-IND_13") (pintype "passive"))
    )
    (net (code "128") (name "SGND") (class "Default")
      (node (ref "C21") (pin "1") (pinfunction "1_1") (pintype "passive"))
      (node (ref "C22") (pin "1") (pinfunction "1_1") (pintype "passive"))
      (node (ref "C23") (pin "2") (pinfunction "2_2") (pintype "passive"))
      (node (ref "C24") (pin "2") (pinfunction "2_2") (pintype "passive"))
      (node (ref "C25") (pin "2") (pinfunction "2_2") (pintype "passive"))
      (node (ref "C26") (pin "2") (pinfunction "2_2") (pintype "passive"))
      (node (ref "C27") (pin "2") (pinfunction "2_2") (pintype "passive"))
      (node (ref "C28") (pin "2") (pinfunction "2_2") (pintype "passive"))
      (node (ref "C29") (pin "2") (pinfunction "2_2") (pintype "passive"))
      (node (ref "C30") (pin "2") (pinfunction "2_2") (pintype "passive"))
      (node (ref "C31") (pin "1") (pinfunction "1_1") (pintype "passive"))
      (node (ref "C32") (pin "2") (pinfunction "2_2") (pintype "passive"))
      (node (ref "C33") (pin "1") (pinfunction "1_1") (pintype "passive"))
      (node (ref "C34") (pin "2") (pinfunction "2_2") (pintype "passive"))
      (node (ref "C35") (pin "2") (pinfunction "2_2") (pintype "passive"))
      (node (ref "C36") (pin "2") (pinfunction "2_2") (pintype "passive"))
      (node (ref "C37") (pin "2") (pinfunction "2_2") (pintype "passive"))
      (node (ref "C38") (pin "2") (pinfunction "2_2") (pintype "passive"))
      (node (ref "C39") (pin "2") (pinfunction "2_2") (pintype "passive"))
      (node (ref "C40") (pin "2") (pinfunction "2_2") (pintype "passive"))
      (node (ref "C41") (pin "1") (pinfunction "1_1") (pintype "passive"))
      (node (ref "C42") (pin "1") (pinfunction "1_1") (pintype "passive"))
      (node (ref "C43") (pin "1") (pinfunction "1_1") (pintype "passive"))
      (node (ref "C44") (pin "2") (pinfunction "2_2") (pintype "passive"))
      (node (ref "C45") (pin "2") (pinfunction "2_2") (pintype "passive"))
      (node (ref "C46") (pin "2") (pinfunction "2_2") (pintype "passive"))
      (node (ref "C47") (pin "2") (pinfunction "2_2") (pintype "passive"))
      (node (ref "C48") (pin "2") (pinfunction "2_2") (pintype "passive"))
      (node (ref "C49") (pin "2") (pinfunction "2_2") (pintype "passive"))
      (node (ref "C50") (pin "2") (pinfunction "2_2") (pintype "passive"))
      (node (ref "C51") (pin "2") (pinfunction "2_2") (pintype "passive"))
      (node (ref "C52") (pin "1") (pinfunction "1_1") (pintype "passive"))
      (node (ref "C53") (pin "2") (pinfunction "2_2") (pintype "passive"))
      (node (ref "C54") (pin "1") (pinfunction "1_1") (pintype "passive"))
      (node (ref "C55") (pin "2") (pinfunction "2_2") (pintype "passive"))
      (node (ref "C56") (pin "2") (pinfunction "2_2") (pintype "passive"))
      (node (ref "C57") (pin "2") (pinfunction "2_2") (pintype "passive"))
      (node (ref "C58") (pin "2") (pinfunction "2_2") (pintype "passive"))
      (node (ref "C59") (pin "2") (pinfunction "2_2") (pintype "passive"))
      (node (ref "C60") (pin "2") (pinfunction "2_2") (pintype "passive"))
      (node (ref "C61") (pin "2") (pinfunction "2_2") (pintype "passive"))
      (node (ref "C62") (pin "1") (pinfunction "1_1") (pintype "passive"))
      (node (ref "R104") (pin "2") (pinfunction "2_2") (pintype "passive"))
      (node (ref "R105") (pin "2") (pinfunction "2_2") (pintype "passive"))
      (node (ref "R108") (pin "2") (pinfunction "2_2") (pintype "passive"))
      (node (ref "R109") (pin "2") (pinfunction "2_2") (pintype "passive"))
      (node (ref "R118") (pin "2") (pinfunction "2_2") (pintype "passive"))
      (node (ref "R119") (pin "2") (pinfunction "2_2") (pintype "passive"))
      (node (ref "R122") (pin "2") (pinfunction "2_2") (pintype "passive"))
      (node (ref "R123") (pin "2") (pinfunction "2_2") (pintype "passive"))
      (node (ref "R126") (pin "2") (pinfunction "2_2") (pintype "passive"))
      (node (ref "R127") (pin "2") (pinfunction "2_2") (pintype "passive"))
      (node (ref "R137") (pin "2") (pinfunction "2_2") (pintype "passive"))
      (node (ref "R138") (pin "2") (pinfunction "2_2") (pintype "passive"))
      (node (ref "R148") (pin "2") (pinfunction "2_2") (pintype "passive"))
      (node (ref "R149") (pin "2") (pinfunction "2_2") (pintype "passive"))
      (node (ref "R152") (pin "2") (pinfunction "2_2") (pintype "passive"))
      (node (ref "R153") (pin "2") (pinfunction "2_2") (pintype "passive"))
      (node (ref "R162") (pin "2") (pinfunction "2_2") (pintype "passive"))
      (node (ref "R163") (pin "2") (pinfunction "2_2") (pintype "passive"))
      (node (ref "R166") (pin "2") (pinfunction "2_2") (pintype "passive"))
      (node (ref "R167") (pin "2") (pinfunction "2_2") (pintype "passive"))
      (node (ref "R82") (pin "2") (pinfunction "2_2") (pintype "passive"))
      (node (ref "R83") (pin "2") (pinfunction "2_2") (pintype "passive"))
      (node (ref "R97") (pin "2") (pinfunction "2_2") (pintype "passive"))
      (node (ref "R98") (pin "2") (pinfunction "2_2") (pintype "passive"))
      (node (ref "U11") (pin "10") (pinfunction "GND_10") (pintype "passive"))
      (node (ref "U11") (pin "9") (pinfunction "OD_9") (pintype "passive"))
      (node (ref "U12") (pin "10") (pinfunction "GND_10") (pintype "passive"))
      (node (ref "U12") (pin "9") (pinfunction "OD_9") (pintype "passive"))
      (node (ref "U14") (pin "10") (pinfunction "GND_10") (pintype "passive"))
      (node (ref "U14") (pin "9") (pinfunction "OD_9") (pintype "passive"))
      (node (ref "U15") (pin "10") (pinfunction "GND_10") (pintype "passive"))
      (node (ref "U15") (pin "9") (pinfunction "OD_9") (pintype "passive"))
      (node (ref "U16") (pin "14") (pinfunction "A1_14") (pintype "passive"))
      (node (ref "U16") (pin "15") (pinfunction "~{ENABLE}_15") (pintype "passive"))
      (node (ref "U16") (pin "5") (pinfunction "VrefL_5") (pintype "passive"))
      (node (ref "U16") (pin "6") (pinfunction "GND_6") (pintype "passive"))
      (node (ref "U18") (pin "10") (pinfunction "GND_10") (pintype "passive"))
      (node (ref "U18") (pin "9") (pinfunction "OD_9") (pintype "passive"))
      (node (ref "U19") (pin "10") (pinfunction "GND_10") (pintype "passive"))
      (node (ref "U19") (pin "9") (pinfunction "OD_9") (pintype "passive"))
      (node (ref "U7") (pin "10") (pinfunction "GND_10") (pintype "passive"))
      (node (ref "U7") (pin "9") (pinfunction "OD_9") (pintype "passive"))
      (node (ref "U8") (pin "10") (pinfunction "GND_10") (pintype "passive"))
      (node (ref "U8") (pin "9") (pinfunction "OD_9") (pintype "passive"))
      (node (ref "U9") (pin "13") (pinfunction "A0_13") (pintype "passive"))
      (node (ref "U9") (pin "14") (pinfunction "A1_14") (pintype "passive"))
      (node (ref "U9") (pin "15") (pinfunction "~{ENABLE}_15") (pintype "passive"))
      (node (ref "U9") (pin "5") (pinfunction "VrefL_5") (pintype "passive"))
      (node (ref "U9") (pin "6") (pinfunction "GND_6") (pintype "passive"))
    )
    (net (code "129") (name "VCC5V") (class "Default")
      (node (ref "U16") (pin "4") (pinfunction "AVDD_4") (pintype "passive"))
      (node (ref "U9") (pin "4") (pinfunction "AVDD_4") (pintype "passive"))
    )
    (net (code "130") (name "VDD3.3V") (class "Default")
      (node (ref "U16") (pin "12") (pinfunction "IOVDD_12") (pintype "passive"))
      (node (ref "U16") (pin "13") (pinfunction "A0_13") (pintype "passive"))
      (node (ref "U9") (pin "12") (pinfunction "IOVDD_12") (pintype "passive"))
    )
    (net (code "131") (name "unconnected-(U7-~{EF}-Pad8)") (class "Default")
      (node (ref "U7") (pin "8") (pinfunction "~{EF}_8") (pintype "passive"))
    )
    (net (code "132") (name "unconnected-(U8-~{EF}-Pad8)") (class "Default")
      (node (ref "U8") (pin "8") (pinfunction "~{EF}_8") (pintype "passive"))
    )
    (net (code "133") (name "unconnected-(U11-~{EF}-Pad8)") (class "Default")
      (node (ref "U11") (pin "8") (pinfunction "~{EF}_8") (pintype "passive"))
    )
    (net (code "134") (name "unconnected-(U12-~{EF}-Pad8)") (class "Default")
      (node (ref "U12") (pin "8") (pinfunction "~{EF}_8") (pintype "passive"))
    )
    (net (code "135") (name "unconnected-(U14-~{EF}-Pad8)") (class "Default")
      (node (ref "U14") (pin "8") (pinfunction "~{EF}_8") (pintype "passive"))
    )
    (net (code "136") (name "unconnected-(U15-~{EF}-Pad8)") (class "Default")
      (node (ref "U15") (pin "8") (pinfunction "~{EF}_8") (pintype "passive"))
    )
    (net (code "137") (name "unconnected-(U18-~{EF}-Pad8)") (class "Default")
      (node (ref "U18") (pin "8") (pinfunction "~{EF}_8") (pintype "passive"))
    )
    (net (code "138") (name "unconnected-(U19-~{EF}-Pad8)") (class "Default")
      (node (ref "U19") (pin "8") (pinfunction "~{EF}_8") (pintype "passive"))
    )
  )
)
